# TRIWHEEL.net
KiCad netlist of a schematic drawn in EAGLE
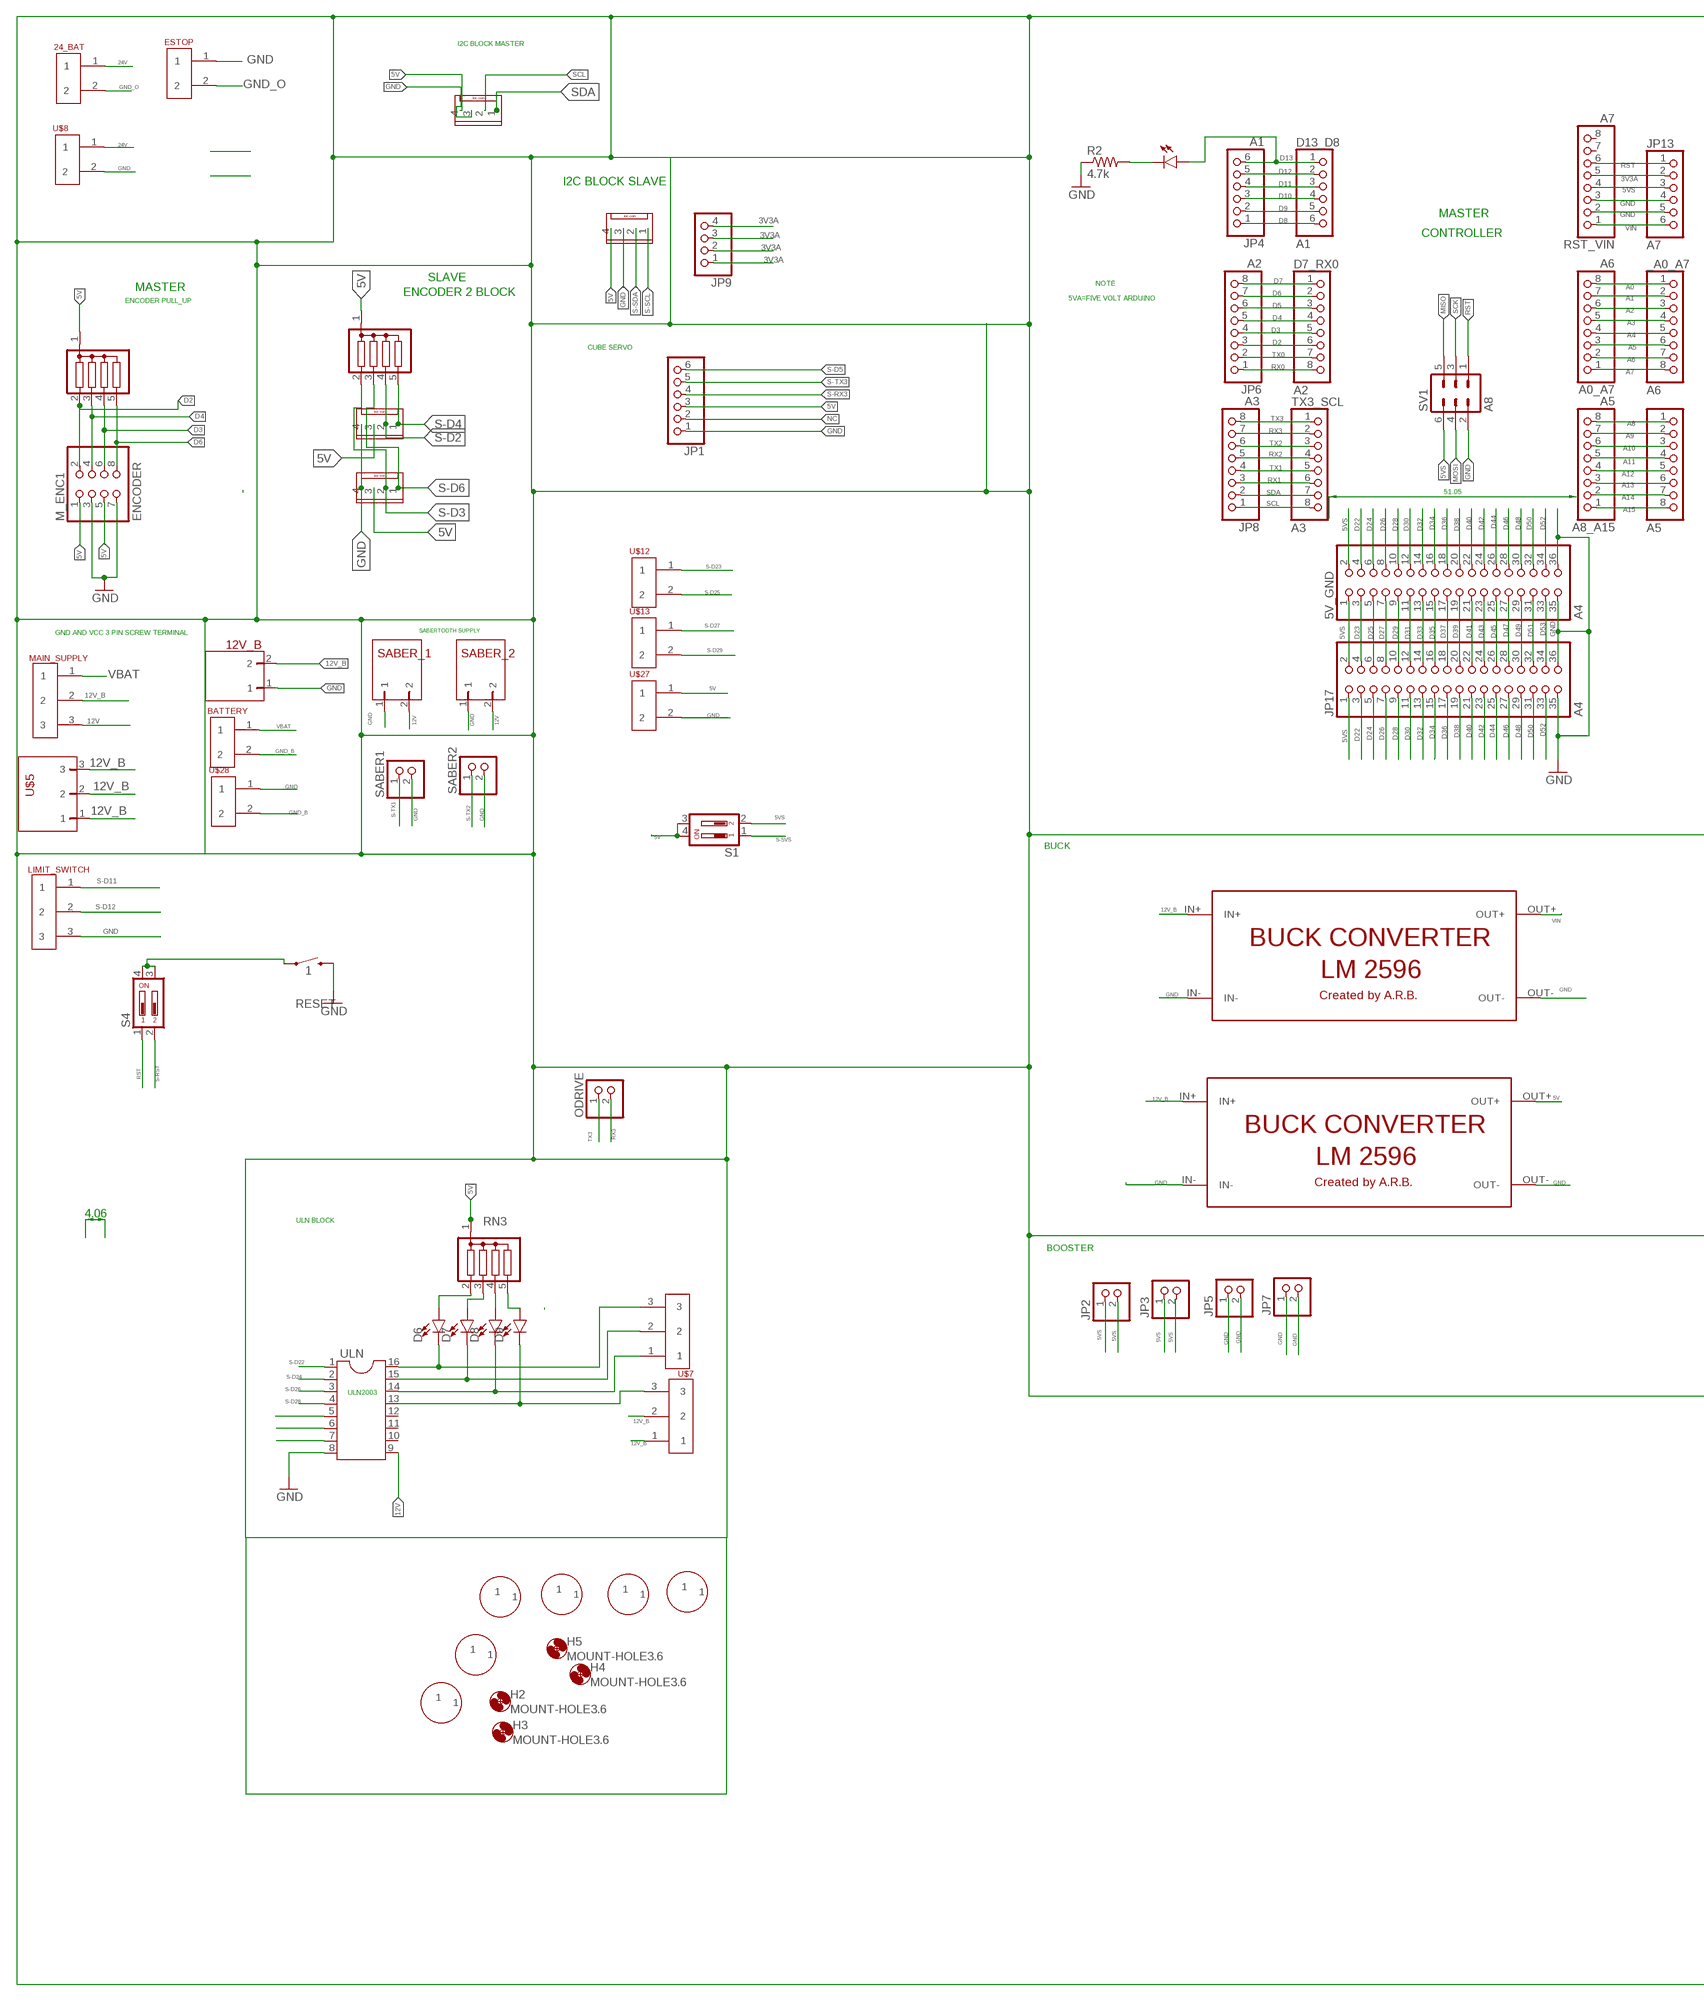
[diagram p0: schematic, sheet 1, part 1 of 2]
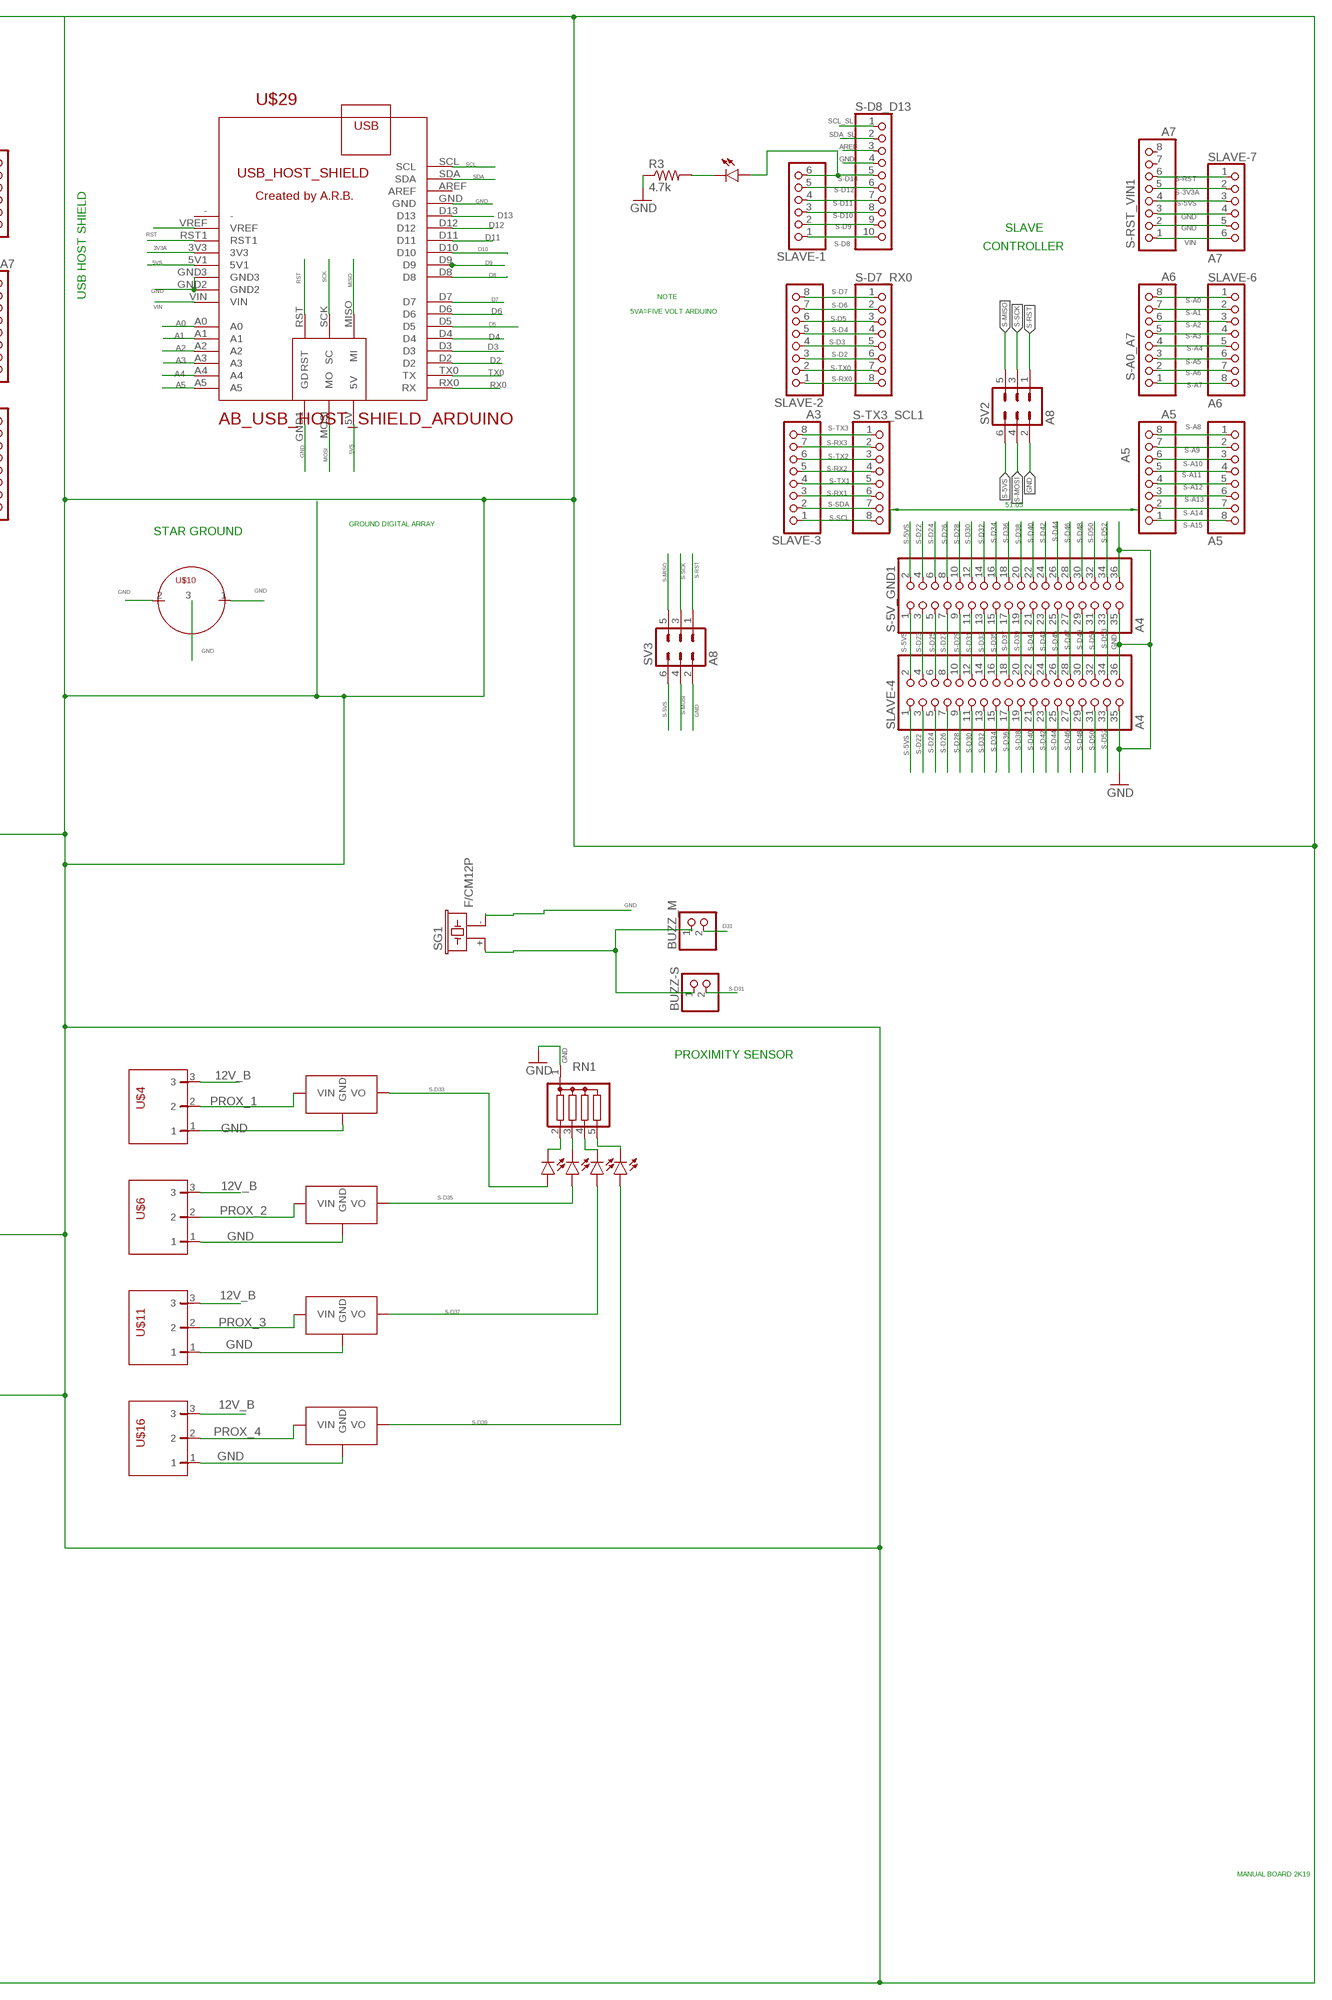
[diagram p1: schematic, sheet 1, part 2 of 2]

(export (version "E")
  (design (tool "Eeschema 10.0.6"))
  (components
    (comp (ref "5V_GND")
      (value "A4")
      (footprint "eagle-import:2X18")
      (libsource (lib "eagle-import") (part "PINHD-2X18"))
    )
    (comp (ref "12V_B")
      (value "AB_RIGHT_TER_BLK")
      (footprint "eagle-import:AB_RIGHT_TER_BLK")
      (libsource (lib "eagle-import") (part "AB_RIGHT_TER_BLK"))
    )
    (comp (ref "24_BAT")
      (value "AB_SCREW_TERMINAL_5MM_2PIN")
      (footprint "eagle-import:AB_SCREW_TERMINAL_5MM_2PIN")
      (libsource (lib "eagle-import") (part "AB_SCREW_TERMINAL_5MM_2PIN"))
    )
    (comp (ref "A0_A7")
      (value "A6")
      (footprint "eagle-import:1X08")
      (libsource (lib "eagle-import") (part "PINHD-1X8"))
    )
    (comp (ref "A5")
      (value "A5")
      (footprint "eagle-import:1X08")
      (libsource (lib "eagle-import") (part "PINHD-1X8"))
    )
    (comp (ref "A8_A15")
      (value "A5")
      (footprint "eagle-import:1X08")
      (libsource (lib "eagle-import") (part "PINHD-1X8"))
    )
    (comp (ref "BATTERY")
      (value "AB_SCREW_TERMINAL_5MM_2PIN")
      (footprint "eagle-import:AB_SCREW_TERMINAL_5MM_2PIN")
      (libsource (lib "eagle-import") (part "AB_SCREW_TERMINAL_5MM_2PIN"))
    )
    (comp (ref "BUZZ-S")
      (value "PINHD-1X2")
      (footprint "eagle-import:1X02")
      (libsource (lib "eagle-import") (part "PINHD-1X2"))
    )
    (comp (ref "BUZZ_M")
      (value "PINHD-1X2")
      (footprint "eagle-import:1X02")
      (libsource (lib "eagle-import") (part "PINHD-1X2"))
    )
    (comp (ref "D1")
      (value "LED-3MM-NO_SILK")
      (footprint "eagle-import:LED_3MM-NS")
      (libsource (lib "eagle-import") (part "LED-3MM-NO_SILK"))
    )
    (comp (ref "D2")
      (value "LED-3MM-NO_SILK")
      (footprint "eagle-import:LED_3MM-NS")
      (libsource (lib "eagle-import") (part "LED-3MM-NO_SILK"))
    )
    (comp (ref "D3")
      (value "LED-3MM-NO_SILK")
      (footprint "eagle-import:LED_3MM-NS")
      (libsource (lib "eagle-import") (part "LED-3MM-NO_SILK"))
    )
    (comp (ref "D4")
      (value "LED-3MM-NO_SILK")
      (footprint "eagle-import:LED_3MM-NS")
      (libsource (lib "eagle-import") (part "LED-3MM-NO_SILK"))
    )
    (comp (ref "D5")
      (value "LED-3MM-NO_SILK")
      (footprint "eagle-import:LED_3MM-NS")
      (libsource (lib "eagle-import") (part "LED-3MM-NO_SILK"))
    )
    (comp (ref "D6")
      (value "LED-3MM-NO_SILK")
      (footprint "eagle-import:LED_3MM-NS")
      (libsource (lib "eagle-import") (part "LED-3MM-NO_SILK"))
    )
    (comp (ref "D7")
      (value "LED-3MM-NO_SILK")
      (footprint "eagle-import:LED_3MM-NS")
      (libsource (lib "eagle-import") (part "LED-3MM-NO_SILK"))
    )
    (comp (ref "D7_RX0")
      (value "A2")
      (footprint "eagle-import:1X08")
      (libsource (lib "eagle-import") (part "PINHD-1X8"))
    )
    (comp (ref "D8")
      (value "LED-3MM-NO_SILK")
      (footprint "eagle-import:LED_3MM-NS")
      (libsource (lib "eagle-import") (part "LED-3MM-NO_SILK"))
    )
    (comp (ref "D9")
      (value "LED-3MM-NO_SILK")
      (footprint "eagle-import:LED_3MM-NS")
      (libsource (lib "eagle-import") (part "LED-3MM-NO_SILK"))
    )
    (comp (ref "D13")
      (value "LED-3MM-NO_SILK")
      (footprint "eagle-import:LED_3MM-NS")
      (libsource (lib "eagle-import") (part "LED-3MM-NO_SILK"))
    )
    (comp (ref "D13_D8")
      (value "A1")
      (footprint "eagle-import:1X06")
      (libsource (lib "eagle-import") (part "PINHD-1X6"))
    )
    (comp (ref "ESTOP")
      (value "AB_SCREW_TERMINAL_5MM_2PIN")
      (footprint "eagle-import:AB_SCREW_TERMINAL_5MM_2PIN")
      (libsource (lib "eagle-import") (part "AB_SCREW_TERMINAL_5MM_2PIN"))
    )
    (comp (ref "H2")
      (value "MOUNT-HOLE3.6")
      (footprint "eagle-import:3,6")
      (libsource (lib "eagle-import") (part "MOUNT-HOLE3.6"))
    )
    (comp (ref "H3")
      (value "MOUNT-HOLE3.6")
      (footprint "eagle-import:3,6")
      (libsource (lib "eagle-import") (part "MOUNT-HOLE3.6"))
    )
    (comp (ref "H4")
      (value "MOUNT-HOLE3.6")
      (footprint "eagle-import:3,6")
      (libsource (lib "eagle-import") (part "MOUNT-HOLE3.6"))
    )
    (comp (ref "H5")
      (value "MOUNT-HOLE3.6")
      (footprint "eagle-import:3,6")
      (libsource (lib "eagle-import") (part "MOUNT-HOLE3.6"))
    )
    (comp (ref "IMU_BLOCK")
      (value "AB_4PIN_LOC_CONNECTOR")
      (footprint "eagle-import:AB_4PIN_LOC_CONNECTOR")
      (libsource (lib "eagle-import") (part "AB_4PIN_LOC_CONNECTOR"))
    )
    (comp (ref "IMU_BLOCK-M")
      (value "AB_4PIN_LOC_CONNECTOR")
      (footprint "eagle-import:AB_4PIN_LOC_CONNECTOR")
      (libsource (lib "eagle-import") (part "AB_4PIN_LOC_CONNECTOR"))
    )
    (comp (ref "JP")
      (value "A5")
      (footprint "eagle-import:1X08")
      (libsource (lib "eagle-import") (part "PINHD-1X8"))
    )
    (comp (ref "JP1")
      (value "PINHD-1X6")
      (footprint "eagle-import:1X06")
      (libsource (lib "eagle-import") (part "PINHD-1X6"))
    )
    (comp (ref "JP2")
      (value "PINHD-1X2")
      (footprint "eagle-import:1X02")
      (libsource (lib "eagle-import") (part "PINHD-1X2"))
    )
    (comp (ref "JP3")
      (value "PINHD-1X2")
      (footprint "eagle-import:1X02")
      (libsource (lib "eagle-import") (part "PINHD-1X2"))
    )
    (comp (ref "JP4")
      (value "A1")
      (footprint "eagle-import:1X06")
      (libsource (lib "eagle-import") (part "PINHD-1X6"))
    )
    (comp (ref "JP5")
      (value "PINHD-1X2")
      (footprint "eagle-import:1X02")
      (libsource (lib "eagle-import") (part "PINHD-1X2"))
    )
    (comp (ref "JP6")
      (value "A2")
      (footprint "eagle-import:1X08")
      (libsource (lib "eagle-import") (part "PINHD-1X8"))
    )
    (comp (ref "JP7")
      (value "PINHD-1X2")
      (footprint "eagle-import:1X02")
      (libsource (lib "eagle-import") (part "PINHD-1X2"))
    )
    (comp (ref "JP8")
      (value "A3")
      (footprint "eagle-import:1X08")
      (libsource (lib "eagle-import") (part "PINHD-1X8"))
    )
    (comp (ref "JP9")
      (value "PINHD-1X4")
      (footprint "eagle-import:1X04")
      (libsource (lib "eagle-import") (part "PINHD-1X4"))
    )
    (comp (ref "JP13")
      (value "A7")
      (footprint "eagle-import:1X06")
      (libsource (lib "eagle-import") (part "PINHD-1X6"))
    )
    (comp (ref "JP17")
      (value "A4")
      (footprint "eagle-import:2X18")
      (libsource (lib "eagle-import") (part "PINHD-2X18"))
    )
    (comp (ref "LIMIT_SWITCH")
      (value "AB_SCREW_TER_5MM_3PIN")
      (footprint "eagle-import:AB_SCREW_TER_5MM_3PIN")
      (libsource (lib "eagle-import") (part "AB_SCREW_TER_5MM_3PIN"))
    )
    (comp (ref "MAIN_SUPPLY")
      (value "AB_SCREW_TER_5MM_3PIN")
      (footprint "eagle-import:AB_SCREW_TER_5MM_3PIN")
      (libsource (lib "eagle-import") (part "AB_SCREW_TER_5MM_3PIN"))
    )
    (comp (ref "MAIN_SUPPLY1")
      (value "AB_SCREW_TER_5MM_3PIN")
      (footprint "eagle-import:AB_SCREW_TER_5MM_3PIN")
      (libsource (lib "eagle-import") (part "AB_SCREW_TER_5MM_3PIN"))
    )
    (comp (ref "M_ENC1")
      (value "ENCODER")
      (footprint "eagle-import:2X04")
      (libsource (lib "eagle-import") (part "PINHD-2X4"))
    )
    (comp (ref "ODRIVE")
      (value "PINHD-1X2")
      (footprint "eagle-import:1X02")
      (libsource (lib "eagle-import") (part "PINHD-1X2"))
    )
    (comp (ref "PULL_RESISTOR-M")
      (value "G04R")
      (footprint "eagle-import:SIL5")
      (libsource (lib "eagle-import") (part "G04R"))
    )
    (comp (ref "R2")
      (value "4.7k")
      (footprint "eagle-import:0204_7")
      (libsource (lib "eagle-import") (part "R-US_0204/7"))
    )
    (comp (ref "R3")
      (value "4.7k")
      (footprint "eagle-import:0204_7")
      (libsource (lib "eagle-import") (part "R-US_0204/7"))
    )
    (comp (ref "RESET")
      (value "1")
      (footprint "eagle-import:TACTILE_SWITCH_PTH_6.0MM")
      (libsource (lib "eagle-import") (part "MOMENTARY-SWITCH-SPST-PTH-6.0MM"))
    )
    (comp (ref "RN1")
      (value "G04R")
      (footprint "eagle-import:SIL5")
      (libsource (lib "eagle-import") (part "G04R"))
    )
    (comp (ref "RN3")
      (value "G04R")
      (footprint "eagle-import:SIL5")
      (libsource (lib "eagle-import") (part "G04R"))
    )
    (comp (ref "RST_VIN")
      (value "A7")
      (footprint "eagle-import:1X08")
      (libsource (lib "eagle-import") (part "PINHD-1X8"))
    )
    (comp (ref "S-5V_GND1")
      (value "A4")
      (footprint "eagle-import:2X18")
      (libsource (lib "eagle-import") (part "PINHD-2X18"))
    )
    (comp (ref "S-A0_A7")
      (value "A6")
      (footprint "eagle-import:1X08")
      (libsource (lib "eagle-import") (part "PINHD-1X8"))
    )
    (comp (ref "S-D7_RX0")
      (value "A2")
      (footprint "eagle-import:1X08")
      (libsource (lib "eagle-import") (part "PINHD-1X8"))
    )
    (comp (ref "S-D8_D13")
      (value "PINHD-1X10")
      (footprint "eagle-import:1X10")
      (libsource (lib "eagle-import") (part "PINHD-1X10"))
    )
    (comp (ref "S-ENC")
      (value "G04R")
      (footprint "eagle-import:SIL5")
      (libsource (lib "eagle-import") (part "G04R"))
    )
    (comp (ref "S-RST_VIN1")
      (value "A7")
      (footprint "eagle-import:1X08")
      (libsource (lib "eagle-import") (part "PINHD-1X8"))
    )
    (comp (ref "S-TX3_SCL1")
      (value "A3")
      (footprint "eagle-import:1X08")
      (libsource (lib "eagle-import") (part "PINHD-1X8"))
    )
    (comp (ref "S1")
      (value "DIP02YL")
      (footprint "eagle-import:DIP02YL")
      (libsource (lib "eagle-import") (part "DIP02YL"))
    )
    (comp (ref "S4")
      (value "DIP02YL")
      (footprint "eagle-import:DIP02YL")
      (libsource (lib "eagle-import") (part "DIP02YL"))
    )
    (comp (ref "SABER1")
      (value "PINHD-1X2")
      (footprint "eagle-import:1X02")
      (libsource (lib "eagle-import") (part "PINHD-1X2"))
    )
    (comp (ref "SABER2")
      (value "PINHD-1X2")
      (footprint "eagle-import:1X02")
      (libsource (lib "eagle-import") (part "PINHD-1X2"))
    )
    (comp (ref "SABER_1")
      (value "AB_RIGHT_TER_BLK")
      (footprint "eagle-import:AB_RIGHT_TER_BLK")
      (libsource (lib "eagle-import") (part "AB_RIGHT_TER_BLK"))
    )
    (comp (ref "SABER_2")
      (value "AB_RIGHT_TER_BLK")
      (footprint "eagle-import:AB_RIGHT_TER_BLK")
      (libsource (lib "eagle-import") (part "AB_RIGHT_TER_BLK"))
    )
    (comp (ref "SG1")
      (value "F/CM12P")
      (footprint "eagle-import:F_CM12P")
      (libsource (lib "eagle-import") (part "F/CM12P"))
    )
    (comp (ref "SLAVE-1")
      (value "A1")
      (footprint "eagle-import:1X06")
      (libsource (lib "eagle-import") (part "PINHD-1X6"))
    )
    (comp (ref "SLAVE-2")
      (value "A2")
      (footprint "eagle-import:1X08")
      (libsource (lib "eagle-import") (part "PINHD-1X8"))
    )
    (comp (ref "SLAVE-3")
      (value "A3")
      (footprint "eagle-import:1X08")
      (libsource (lib "eagle-import") (part "PINHD-1X8"))
    )
    (comp (ref "SLAVE-4")
      (value "A4")
      (footprint "eagle-import:2X18")
      (libsource (lib "eagle-import") (part "PINHD-2X18"))
    )
    (comp (ref "SLAVE-6")
      (value "A6")
      (footprint "eagle-import:1X08")
      (libsource (lib "eagle-import") (part "PINHD-1X8"))
    )
    (comp (ref "SLAVE-7")
      (value "A7")
      (footprint "eagle-import:1X06")
      (libsource (lib "eagle-import") (part "PINHD-1X6"))
    )
    (comp (ref "SV1")
      (value "A8")
      (footprint "eagle-import:MA03-2")
      (libsource (lib "eagle-import") (part "MA03-2"))
    )
    (comp (ref "SV2")
      (value "A8")
      (footprint "eagle-import:MA03-2")
      (libsource (lib "eagle-import") (part "MA03-2"))
    )
    (comp (ref "SV3")
      (value "A8")
      (footprint "eagle-import:MA03-2")
      (libsource (lib "eagle-import") (part "MA03-2"))
    )
    (comp (ref "S_A8_A15")
      (value "A5")
      (footprint "eagle-import:1X08")
      (libsource (lib "eagle-import") (part "PINHD-1X8"))
    )
    (comp (ref "TX3_SCL")
      (value "A3")
      (footprint "eagle-import:1X08")
      (libsource (lib "eagle-import") (part "PINHD-1X8"))
    )
    (comp (ref "U$1")
      (value "AB_LM2596_BUCK_CONVERTER")
      (footprint "eagle-import:AB_LM2596_BUCK_CONVERTER")
      (libsource (lib "eagle-import") (part "AB_LM2596_BUCK_CONVERTER"))
    )
    (comp (ref "U$2")
      (value "AB_LM2596_BUCK_CONVERTER")
      (footprint "eagle-import:AB_LM2596_BUCK_CONVERTER")
      (libsource (lib "eagle-import") (part "AB_LM2596_BUCK_CONVERTER"))
    )
    (comp (ref "U$4")
      (value "AB_RIGHT_TER_BLK_3PIN")
      (footprint "eagle-import:AB_RIGHT_TER_BLK_3PIN")
      (libsource (lib "eagle-import") (part "AB_RIGHT_TER_BLK_3PIN"))
    )
    (comp (ref "U$5")
      (value "AB_RIGHT_TER_BLK_3PIN")
      (footprint "eagle-import:AB_RIGHT_TER_BLK_3PIN")
      (libsource (lib "eagle-import") (part "AB_RIGHT_TER_BLK_3PIN"))
    )
    (comp (ref "U$6")
      (value "AB_RIGHT_TER_BLK_3PIN")
      (footprint "eagle-import:AB_RIGHT_TER_BLK_3PIN")
      (libsource (lib "eagle-import") (part "AB_RIGHT_TER_BLK_3PIN"))
    )
    (comp (ref "U$7")
      (value "AB_SCREW_TER_5MM_3PIN")
      (footprint "eagle-import:AB_SCREW_TER_5MM_3PIN")
      (libsource (lib "eagle-import") (part "AB_SCREW_TER_5MM_3PIN"))
    )
    (comp (ref "U$8")
      (value "AB_SCREW_TERMINAL_5MM_2PIN")
      (footprint "eagle-import:AB_SCREW_TERMINAL_5MM_2PIN")
      (libsource (lib "eagle-import") (part "AB_SCREW_TERMINAL_5MM_2PIN"))
    )
    (comp (ref "U$9")
      (value "AB_PLATED_DRILL_160MIL")
      (footprint "eagle-import:AB_PLATED_DRILL_160MIL")
      (libsource (lib "eagle-import") (part "AB_PLATED_DRILL_160MIL"))
    )
    (comp (ref "U$10")
      (value "AB_JOINT_GND")
      (footprint "eagle-import:AB_JOINT_GND")
      (libsource (lib "eagle-import") (part "AB_JOINT_GND"))
    )
    (comp (ref "U$11")
      (value "AB_RIGHT_TER_BLK_3PIN")
      (footprint "eagle-import:AB_RIGHT_TER_BLK_3PIN")
      (libsource (lib "eagle-import") (part "AB_RIGHT_TER_BLK_3PIN"))
    )
    (comp (ref "U$12")
      (value "AB_SCREW_TERMINAL_5MM_2PIN")
      (footprint "eagle-import:AB_SCREW_TERMINAL_5MM_2PIN")
      (libsource (lib "eagle-import") (part "AB_SCREW_TERMINAL_5MM_2PIN"))
    )
    (comp (ref "U$13")
      (value "AB_SCREW_TERMINAL_5MM_2PIN")
      (footprint "eagle-import:AB_SCREW_TERMINAL_5MM_2PIN")
      (libsource (lib "eagle-import") (part "AB_SCREW_TERMINAL_5MM_2PIN"))
    )
    (comp (ref "U$15")
      (value "AB_PLATED_DRILL_160MIL")
      (footprint "eagle-import:AB_PLATED_DRILL_160MIL")
      (libsource (lib "eagle-import") (part "AB_PLATED_DRILL_160MIL"))
    )
    (comp (ref "U$16")
      (value "AB_RIGHT_TER_BLK_3PIN")
      (footprint "eagle-import:AB_RIGHT_TER_BLK_3PIN")
      (libsource (lib "eagle-import") (part "AB_RIGHT_TER_BLK_3PIN"))
    )
    (comp (ref "U$17")
      (value "AB_7805_FLAT")
      (footprint "eagle-import:AB_7805_FLAT")
      (libsource (lib "eagle-import") (part "AB_7805_FLAT"))
    )
    (comp (ref "U$18")
      (value "AB_7805_FLAT")
      (footprint "eagle-import:AB_7805_FLAT")
      (libsource (lib "eagle-import") (part "AB_7805_FLAT"))
    )
    (comp (ref "U$19")
      (value "AB_7805_FLAT")
      (footprint "eagle-import:AB_7805_FLAT")
      (libsource (lib "eagle-import") (part "AB_7805_FLAT"))
    )
    (comp (ref "U$20")
      (value "AB_7805_FLAT")
      (footprint "eagle-import:AB_7805_FLAT")
      (libsource (lib "eagle-import") (part "AB_7805_FLAT"))
    )
    (comp (ref "U$21")
      (value "en1")
      (footprint "eagle-import:AB_4PIN_LOC_CONNECTOR")
      (libsource (lib "eagle-import") (part "AB_4PIN_LOC_CONNECTOR"))
    )
    (comp (ref "U$22")
      (value "en2")
      (footprint "eagle-import:AB_4PIN_LOC_CONNECTOR")
      (libsource (lib "eagle-import") (part "AB_4PIN_LOC_CONNECTOR"))
    )
    (comp (ref "U$23")
      (value "AB_PLATED_DRILL_160MIL")
      (footprint "eagle-import:AB_PLATED_DRILL_160MIL")
      (libsource (lib "eagle-import") (part "AB_PLATED_DRILL_160MIL"))
    )
    (comp (ref "U$24")
      (value "AB_PLATED_DRILL_160MIL")
      (footprint "eagle-import:AB_PLATED_DRILL_160MIL")
      (libsource (lib "eagle-import") (part "AB_PLATED_DRILL_160MIL"))
    )
    (comp (ref "U$25")
      (value "AB_PLATED_DRILL_160MIL")
      (footprint "eagle-import:AB_PLATED_DRILL_160MIL")
      (libsource (lib "eagle-import") (part "AB_PLATED_DRILL_160MIL"))
    )
    (comp (ref "U$26")
      (value "AB_PLATED_DRILL_160MIL")
      (footprint "eagle-import:AB_PLATED_DRILL_160MIL")
      (libsource (lib "eagle-import") (part "AB_PLATED_DRILL_160MIL"))
    )
    (comp (ref "U$27")
      (value "AB_SCREW_TERMINAL_5MM_2PIN")
      (footprint "eagle-import:AB_SCREW_TERMINAL_5MM_2PIN")
      (libsource (lib "eagle-import") (part "AB_SCREW_TERMINAL_5MM_2PIN"))
    )
    (comp (ref "U$28")
      (value "AB_SCREW_TERMINAL_5MM_2PIN")
      (footprint "eagle-import:AB_SCREW_TERMINAL_5MM_2PIN")
      (libsource (lib "eagle-import") (part "AB_SCREW_TERMINAL_5MM_2PIN"))
    )
    (comp (ref "U$29")
      (value "AB_USB_HOST_SHIELD_ARDUINO")
      (footprint "eagle-import:AB_USB_HOST_SHIELD_ARDUINO")
      (libsource (lib "eagle-import") (part "AB_USB_HOST_SHIELD_ARDUINO"))
    )
    (comp (ref "ULN")
      (value "DIL16")
      (footprint "eagle-import:DIL16")
      (libsource (lib "eagle-import") (part "DIL16"))
    )
    (comp (ref "_A0_A7")
      (value "A6")
      (footprint "eagle-import:1X08")
      (libsource (lib "eagle-import") (part "PINHD-1X8"))
    )
  )
  (nets
    (net (code "1") (name "/3V3A") (class "Default")
      (node (ref "JP13") (pin "2") (pinfunction "2_2") (pintype "passive"))
      (node (ref "JP9") (pin "1") (pinfunction "1_1") (pintype "passive"))
      (node (ref "JP9") (pin "2") (pinfunction "2_2") (pintype "passive"))
      (node (ref "JP9") (pin "3") (pinfunction "3_3") (pintype "passive"))
      (node (ref "JP9") (pin "4") (pinfunction "4_4") (pintype "passive"))
      (node (ref "RST_VIN") (pin "5") (pinfunction "5_5") (pintype "passive"))
      (node (ref "U$29") (pin "3V3") (pinfunction "3V3_3V3") (pintype "bidirectional"))
    )
    (net (code "2") (name "/24V") (class "Default")
      (node (ref "24_BAT") (pin "1") (pinfunction "1_1") (pintype "bidirectional"))
      (node (ref "U$8") (pin "1") (pinfunction "1_1") (pintype "bidirectional"))
    )
    (net (code "3") (name "/A0") (class "Default")
      (node (ref "A0_A7") (pin "8") (pinfunction "8_8") (pintype "passive"))
      (node (ref "U$29") (pin "A0") (pinfunction "A0_A0") (pintype "bidirectional"))
      (node (ref "_A0_A7") (pin "1") (pinfunction "1_1") (pintype "passive"))
    )
    (net (code "4") (name "/A1") (class "Default")
      (node (ref "A0_A7") (pin "7") (pinfunction "7_7") (pintype "passive"))
      (node (ref "U$29") (pin "A1") (pinfunction "A1_A1") (pintype "bidirectional"))
      (node (ref "_A0_A7") (pin "2") (pinfunction "2_2") (pintype "passive"))
    )
    (net (code "5") (name "/A2") (class "Default")
      (node (ref "A0_A7") (pin "6") (pinfunction "6_6") (pintype "passive"))
      (node (ref "U$29") (pin "A2") (pinfunction "A2_A2") (pintype "bidirectional"))
      (node (ref "_A0_A7") (pin "3") (pinfunction "3_3") (pintype "passive"))
    )
    (net (code "6") (name "/A3") (class "Default")
      (node (ref "A0_A7") (pin "5") (pinfunction "5_5") (pintype "passive"))
      (node (ref "U$29") (pin "A3") (pinfunction "A3_A3") (pintype "bidirectional"))
      (node (ref "_A0_A7") (pin "4") (pinfunction "4_4") (pintype "passive"))
    )
    (net (code "7") (name "/A4") (class "Default")
      (node (ref "A0_A7") (pin "4") (pinfunction "4_4") (pintype "passive"))
      (node (ref "U$29") (pin "A4") (pinfunction "A4_A4") (pintype "bidirectional"))
      (node (ref "_A0_A7") (pin "5") (pinfunction "5_5") (pintype "passive"))
    )
    (net (code "8") (name "/A5") (class "Default")
      (node (ref "A0_A7") (pin "3") (pinfunction "3_3") (pintype "passive"))
      (node (ref "U$29") (pin "A5") (pinfunction "A5_A5") (pintype "bidirectional"))
      (node (ref "_A0_A7") (pin "6") (pinfunction "6_6") (pintype "passive"))
    )
    (net (code "9") (name "/A6") (class "Default")
      (node (ref "A0_A7") (pin "2") (pinfunction "2_2") (pintype "passive"))
      (node (ref "_A0_A7") (pin "7") (pinfunction "7_7") (pintype "passive"))
    )
    (net (code "10") (name "/A7") (class "Default")
      (node (ref "A0_A7") (pin "1") (pinfunction "1_1") (pintype "passive"))
      (node (ref "_A0_A7") (pin "8") (pinfunction "8_8") (pintype "passive"))
    )
    (net (code "11") (name "/A8") (class "Default")
      (node (ref "A8_A15") (pin "8") (pinfunction "8_8") (pintype "passive"))
      (node (ref "JP") (pin "1") (pinfunction "1_1") (pintype "passive"))
    )
    (net (code "12") (name "/A9") (class "Default")
      (node (ref "A8_A15") (pin "7") (pinfunction "7_7") (pintype "passive"))
      (node (ref "JP") (pin "2") (pinfunction "2_2") (pintype "passive"))
    )
    (net (code "13") (name "/A10") (class "Default")
      (node (ref "A8_A15") (pin "6") (pinfunction "6_6") (pintype "passive"))
      (node (ref "JP") (pin "3") (pinfunction "3_3") (pintype "passive"))
    )
    (net (code "14") (name "/A11") (class "Default")
      (node (ref "A8_A15") (pin "5") (pinfunction "5_5") (pintype "passive"))
      (node (ref "JP") (pin "4") (pinfunction "4_4") (pintype "passive"))
    )
    (net (code "15") (name "/A12") (class "Default")
      (node (ref "A8_A15") (pin "4") (pinfunction "4_4") (pintype "passive"))
      (node (ref "JP") (pin "5") (pinfunction "5_5") (pintype "passive"))
    )
    (net (code "16") (name "/A13") (class "Default")
      (node (ref "A8_A15") (pin "3") (pinfunction "3_3") (pintype "passive"))
      (node (ref "JP") (pin "6") (pinfunction "6_6") (pintype "passive"))
    )
    (net (code "17") (name "/A14") (class "Default")
      (node (ref "A8_A15") (pin "2") (pinfunction "2_2") (pintype "passive"))
      (node (ref "JP") (pin "7") (pinfunction "7_7") (pintype "passive"))
    )
    (net (code "18") (name "/A15") (class "Default")
      (node (ref "A8_A15") (pin "1") (pinfunction "1_1") (pintype "passive"))
      (node (ref "JP") (pin "8") (pinfunction "8_8") (pintype "passive"))
    )
    (net (code "19") (name "/AREF") (class "Default")
      (node (ref "S-D8_D13") (pin "3") (pinfunction "3_3") (pintype "passive"))
    )
    (net (code "20") (name "/D5") (class "Default")
      (node (ref "D7_RX0") (pin "3") (pinfunction "3_3") (pintype "passive"))
      (node (ref "JP6") (pin "6") (pinfunction "6_6") (pintype "passive"))
      (node (ref "U$29") (pin "D5") (pinfunction "D5_D5") (pintype "bidirectional"))
    )
    (net (code "21") (name "/D7") (class "Default")
      (node (ref "D7_RX0") (pin "1") (pinfunction "1_1") (pintype "passive"))
      (node (ref "JP6") (pin "8") (pinfunction "8_8") (pintype "passive"))
      (node (ref "U$29") (pin "D7") (pinfunction "D7_D7") (pintype "bidirectional"))
    )
    (net (code "22") (name "/D8") (class "Default")
      (node (ref "D13_D8") (pin "6") (pinfunction "6_6") (pintype "passive"))
      (node (ref "JP4") (pin "1") (pinfunction "1_1") (pintype "passive"))
      (node (ref "U$29") (pin "D8") (pinfunction "D8_D8") (pintype "bidirectional"))
    )
    (net (code "23") (name "/D9") (class "Default")
      (node (ref "D13_D8") (pin "5") (pinfunction "5_5") (pintype "passive"))
      (node (ref "JP4") (pin "2") (pinfunction "2_2") (pintype "passive"))
      (node (ref "U$29") (pin "D9") (pinfunction "D9_D9") (pintype "bidirectional"))
    )
    (net (code "24") (name "/D10") (class "Default")
      (node (ref "D13_D8") (pin "4") (pinfunction "4_4") (pintype "passive"))
      (node (ref "JP4") (pin "3") (pinfunction "3_3") (pintype "passive"))
      (node (ref "U$29") (pin "D10") (pinfunction "D10_D10") (pintype "bidirectional"))
    )
    (net (code "25") (name "/D11") (class "Default")
      (node (ref "D13_D8") (pin "3") (pinfunction "3_3") (pintype "passive"))
      (node (ref "JP4") (pin "4") (pinfunction "4_4") (pintype "passive"))
      (node (ref "U$29") (pin "D11") (pinfunction "D11_D11") (pintype "bidirectional"))
    )
    (net (code "26") (name "/D12") (class "Default")
      (node (ref "D13_D8") (pin "2") (pinfunction "2_2") (pintype "passive"))
      (node (ref "JP4") (pin "5") (pinfunction "5_5") (pintype "passive"))
      (node (ref "U$29") (pin "D12") (pinfunction "D12_D12") (pintype "bidirectional"))
    )
    (net (code "27") (name "/D13") (class "Default")
      (node (ref "D13") (pin "A") (pinfunction "A_A") (pintype "passive"))
      (node (ref "D13_D8") (pin "1") (pinfunction "1_1") (pintype "passive"))
      (node (ref "JP4") (pin "6") (pinfunction "6_6") (pintype "passive"))
      (node (ref "U$29") (pin "D13") (pinfunction "D13_D13") (pintype "bidirectional"))
    )
    (net (code "28") (name "/D22") (class "Default")
      (node (ref "5V_GND") (pin "4") (pinfunction "4_4") (pintype "passive"))
      (node (ref "JP17") (pin "3") (pinfunction "3_3") (pintype "passive"))
    )
    (net (code "29") (name "/D23") (class "Default")
      (node (ref "5V_GND") (pin "3") (pinfunction "3_3") (pintype "passive"))
      (node (ref "JP17") (pin "4") (pinfunction "4_4") (pintype "passive"))
    )
    (net (code "30") (name "/D24") (class "Default")
      (node (ref "5V_GND") (pin "6") (pinfunction "6_6") (pintype "passive"))
      (node (ref "JP17") (pin "5") (pinfunction "5_5") (pintype "passive"))
    )
    (net (code "31") (name "/D25") (class "Default")
      (node (ref "5V_GND") (pin "5") (pinfunction "5_5") (pintype "passive"))
      (node (ref "JP17") (pin "6") (pinfunction "6_6") (pintype "passive"))
    )
    (net (code "32") (name "/D26") (class "Default")
      (node (ref "5V_GND") (pin "8") (pinfunction "8_8") (pintype "passive"))
      (node (ref "JP17") (pin "7") (pinfunction "7_7") (pintype "passive"))
    )
    (net (code "33") (name "/D27") (class "Default")
      (node (ref "5V_GND") (pin "7") (pinfunction "7_7") (pintype "passive"))
      (node (ref "JP17") (pin "8") (pinfunction "8_8") (pintype "passive"))
    )
    (net (code "34") (name "/D28") (class "Default")
      (node (ref "5V_GND") (pin "10") (pinfunction "10_10") (pintype "passive"))
      (node (ref "JP17") (pin "9") (pinfunction "9_9") (pintype "passive"))
    )
    (net (code "35") (name "/D29") (class "Default")
      (node (ref "5V_GND") (pin "9") (pinfunction "9_9") (pintype "passive"))
      (node (ref "JP17") (pin "10") (pinfunction "10_10") (pintype "passive"))
    )
    (net (code "36") (name "/D30") (class "Default")
      (node (ref "5V_GND") (pin "12") (pinfunction "12_12") (pintype "passive"))
      (node (ref "JP17") (pin "11") (pinfunction "11_11") (pintype "passive"))
    )
    (net (code "37") (name "/D31") (class "Default")
      (node (ref "5V_GND") (pin "11") (pinfunction "11_11") (pintype "passive"))
      (node (ref "BUZZ_M") (pin "2") (pinfunction "2_2") (pintype "passive"))
      (node (ref "JP17") (pin "12") (pinfunction "12_12") (pintype "passive"))
    )
    (net (code "38") (name "/D32") (class "Default")
      (node (ref "5V_GND") (pin "14") (pinfunction "14_14") (pintype "passive"))
      (node (ref "JP17") (pin "13") (pinfunction "13_13") (pintype "passive"))
    )
    (net (code "39") (name "/D33") (class "Default")
      (node (ref "5V_GND") (pin "13") (pinfunction "13_13") (pintype "passive"))
      (node (ref "JP17") (pin "14") (pinfunction "14_14") (pintype "passive"))
    )
    (net (code "40") (name "/D34") (class "Default")
      (node (ref "5V_GND") (pin "16") (pinfunction "16_16") (pintype "passive"))
      (node (ref "JP17") (pin "15") (pinfunction "15_15") (pintype "passive"))
    )
    (net (code "41") (name "/D35") (class "Default")
      (node (ref "5V_GND") (pin "15") (pinfunction "15_15") (pintype "passive"))
      (node (ref "JP17") (pin "16") (pinfunction "16_16") (pintype "passive"))
    )
    (net (code "42") (name "/D36") (class "Default")
      (node (ref "5V_GND") (pin "18") (pinfunction "18_18") (pintype "passive"))
      (node (ref "JP17") (pin "17") (pinfunction "17_17") (pintype "passive"))
    )
    (net (code "43") (name "/D37") (class "Default")
      (node (ref "5V_GND") (pin "17") (pinfunction "17_17") (pintype "passive"))
      (node (ref "JP17") (pin "18") (pinfunction "18_18") (pintype "passive"))
    )
    (net (code "44") (name "/D38") (class "Default")
      (node (ref "5V_GND") (pin "20") (pinfunction "20_20") (pintype "passive"))
      (node (ref "JP17") (pin "19") (pinfunction "19_19") (pintype "passive"))
    )
    (net (code "45") (name "/D39") (class "Default")
      (node (ref "5V_GND") (pin "19") (pinfunction "19_19") (pintype "passive"))
      (node (ref "JP17") (pin "20") (pinfunction "20_20") (pintype "passive"))
    )
    (net (code "46") (name "/D40") (class "Default")
      (node (ref "5V_GND") (pin "22") (pinfunction "22_22") (pintype "passive"))
      (node (ref "JP17") (pin "21") (pinfunction "21_21") (pintype "passive"))
    )
    (net (code "47") (name "/D41") (class "Default")
      (node (ref "5V_GND") (pin "21") (pinfunction "21_21") (pintype "passive"))
      (node (ref "JP17") (pin "22") (pinfunction "22_22") (pintype "passive"))
    )
    (net (code "48") (name "/D42") (class "Default")
      (node (ref "5V_GND") (pin "24") (pinfunction "24_24") (pintype "passive"))
      (node (ref "JP17") (pin "23") (pinfunction "23_23") (pintype "passive"))
    )
    (net (code "49") (name "/D43") (class "Default")
      (node (ref "5V_GND") (pin "23") (pinfunction "23_23") (pintype "passive"))
      (node (ref "JP17") (pin "24") (pinfunction "24_24") (pintype "passive"))
    )
    (net (code "50") (name "/D44") (class "Default")
      (node (ref "5V_GND") (pin "26") (pinfunction "26_26") (pintype "passive"))
      (node (ref "JP17") (pin "25") (pinfunction "25_25") (pintype "passive"))
    )
    (net (code "51") (name "/D45") (class "Default")
      (node (ref "5V_GND") (pin "25") (pinfunction "25_25") (pintype "passive"))
      (node (ref "JP17") (pin "26") (pinfunction "26_26") (pintype "passive"))
    )
    (net (code "52") (name "/D46") (class "Default")
      (node (ref "5V_GND") (pin "28") (pinfunction "28_28") (pintype "passive"))
      (node (ref "JP17") (pin "27") (pinfunction "27_27") (pintype "passive"))
    )
    (net (code "53") (name "/D47") (class "Default")
      (node (ref "5V_GND") (pin "27") (pinfunction "27_27") (pintype "passive"))
      (node (ref "JP17") (pin "28") (pinfunction "28_28") (pintype "passive"))
    )
    (net (code "54") (name "/D48") (class "Default")
      (node (ref "5V_GND") (pin "30") (pinfunction "30_30") (pintype "passive"))
      (node (ref "JP17") (pin "29") (pinfunction "29_29") (pintype "passive"))
    )
    (net (code "55") (name "/D49") (class "Default")
      (node (ref "5V_GND") (pin "29") (pinfunction "29_29") (pintype "passive"))
      (node (ref "JP17") (pin "30") (pinfunction "30_30") (pintype "passive"))
    )
    (net (code "56") (name "/D50") (class "Default")
      (node (ref "5V_GND") (pin "32") (pinfunction "32_32") (pintype "passive"))
      (node (ref "JP17") (pin "31") (pinfunction "31_31") (pintype "passive"))
    )
    (net (code "57") (name "/D51") (class "Default")
      (node (ref "5V_GND") (pin "31") (pinfunction "31_31") (pintype "passive"))
      (node (ref "JP17") (pin "32") (pinfunction "32_32") (pintype "passive"))
    )
    (net (code "58") (name "/D52") (class "Default")
      (node (ref "5V_GND") (pin "34") (pinfunction "34_34") (pintype "passive"))
      (node (ref "JP17") (pin "33") (pinfunction "33_33") (pintype "passive"))
    )
    (net (code "59") (name "/D53") (class "Default")
      (node (ref "5V_GND") (pin "33") (pinfunction "33_33") (pintype "passive"))
      (node (ref "JP17") (pin "34") (pinfunction "34_34") (pintype "passive"))
    )
    (net (code "60") (name "/GND_B") (class "Default")
      (node (ref "BATTERY") (pin "2") (pinfunction "2_2") (pintype "bidirectional"))
      (node (ref "U$28") (pin "2") (pinfunction "2_2") (pintype "bidirectional"))
    )
    (net (code "61") (name "/GND_O") (class "Default")
      (node (ref "24_BAT") (pin "2") (pinfunction "2_2") (pintype "bidirectional"))
      (node (ref "ESTOP") (pin "2") (pinfunction "2_2") (pintype "bidirectional"))
    )
    (net (code "62") (name "/PROX_1") (class "Default")
      (node (ref "U$17") (pin "1") (pinfunction "VIN_1") (pintype "bidirectional"))
      (node (ref "U$4") (pin "2") (pinfunction "2_2") (pintype "bidirectional"))
    )
    (net (code "63") (name "/PROX_2") (class "Default")
      (node (ref "U$18") (pin "1") (pinfunction "VIN_1") (pintype "bidirectional"))
      (node (ref "U$6") (pin "2") (pinfunction "2_2") (pintype "bidirectional"))
    )
    (net (code "64") (name "/PROX_3") (class "Default")
      (node (ref "U$11") (pin "2") (pinfunction "2_2") (pintype "bidirectional"))
      (node (ref "U$19") (pin "1") (pinfunction "VIN_1") (pintype "bidirectional"))
    )
    (net (code "65") (name "/PROX_4") (class "Default")
      (node (ref "U$16") (pin "2") (pinfunction "2_2") (pintype "bidirectional"))
      (node (ref "U$20") (pin "1") (pinfunction "VIN_1") (pintype "bidirectional"))
    )
    (net (code "66") (name "/RX0") (class "Default")
      (node (ref "D7_RX0") (pin "8") (pinfunction "8_8") (pintype "passive"))
      (node (ref "JP6") (pin "1") (pinfunction "1_1") (pintype "passive"))
      (node (ref "U$29") (pin "RX0") (pinfunction "RX_RX0") (pintype "bidirectional"))
    )
    (net (code "67") (name "/RX1") (class "Default")
      (node (ref "JP8") (pin "3") (pinfunction "3_3") (pintype "passive"))
      (node (ref "TX3_SCL") (pin "6") (pinfunction "6_6") (pintype "passive"))
    )
    (net (code "68") (name "/RX2") (class "Default")
      (node (ref "JP8") (pin "5") (pinfunction "5_5") (pintype "passive"))
      (node (ref "TX3_SCL") (pin "4") (pinfunction "4_4") (pintype "passive"))
    )
    (net (code "69") (name "/RX3") (class "Default")
      (node (ref "JP8") (pin "7") (pinfunction "7_7") (pintype "passive"))
      (node (ref "ODRIVE") (pin "2") (pinfunction "2_2") (pintype "passive"))
      (node (ref "TX3_SCL") (pin "2") (pinfunction "2_2") (pintype "passive"))
    )
    (net (code "70") (name "/S-3V3A") (class "Default")
      (node (ref "S-RST_VIN1") (pin "5") (pinfunction "5_5") (pintype "passive"))
      (node (ref "SLAVE-7") (pin "2") (pinfunction "2_2") (pintype "passive"))
    )
    (net (code "71") (name "/S-A0") (class "Default")
      (node (ref "S-A0_A7") (pin "8") (pinfunction "8_8") (pintype "passive"))
      (node (ref "SLAVE-6") (pin "1") (pinfunction "1_1") (pintype "passive"))
    )
    (net (code "72") (name "/S-A1") (class "Default")
      (node (ref "S-A0_A7") (pin "7") (pinfunction "7_7") (pintype "passive"))
      (node (ref "SLAVE-6") (pin "2") (pinfunction "2_2") (pintype "passive"))
    )
    (net (code "73") (name "/S-A2") (class "Default")
      (node (ref "S-A0_A7") (pin "6") (pinfunction "6_6") (pintype "passive"))
      (node (ref "SLAVE-6") (pin "3") (pinfunction "3_3") (pintype "passive"))
    )
    (net (code "74") (name "/S-A3") (class "Default")
      (node (ref "S-A0_A7") (pin "5") (pinfunction "5_5") (pintype "passive"))
      (node (ref "SLAVE-6") (pin "4") (pinfunction "4_4") (pintype "passive"))
    )
    (net (code "75") (name "/S-A4") (class "Default")
      (node (ref "S-A0_A7") (pin "4") (pinfunction "4_4") (pintype "passive"))
      (node (ref "SLAVE-6") (pin "5") (pinfunction "5_5") (pintype "passive"))
    )
    (net (code "76") (name "/S-A5") (class "Default")
      (node (ref "S-A0_A7") (pin "3") (pinfunction "3_3") (pintype "passive"))
      (node (ref "SLAVE-6") (pin "6") (pinfunction "6_6") (pintype "passive"))
    )
    (net (code "77") (name "/S-A6") (class "Default")
      (node (ref "S-A0_A7") (pin "2") (pinfunction "2_2") (pintype "passive"))
      (node (ref "SLAVE-6") (pin "7") (pinfunction "7_7") (pintype "passive"))
    )
    (net (code "78") (name "/S-A7") (class "Default")
      (node (ref "S-A0_A7") (pin "1") (pinfunction "1_1") (pintype "passive"))
      (node (ref "SLAVE-6") (pin "8") (pinfunction "8_8") (pintype "passive"))
    )
    (net (code "79") (name "/S-A8") (class "Default")
      (node (ref "A5") (pin "8") (pinfunction "8_8") (pintype "passive"))
      (node (ref "S_A8_A15") (pin "1") (pinfunction "1_1") (pintype "passive"))
    )
    (net (code "80") (name "/S-A9") (class "Default")
      (node (ref "A5") (pin "7") (pinfunction "7_7") (pintype "passive"))
      (node (ref "S_A8_A15") (pin "2") (pinfunction "2_2") (pintype "passive"))
    )
    (net (code "81") (name "/S-A10") (class "Default")
      (node (ref "A5") (pin "6") (pinfunction "6_6") (pintype "passive"))
      (node (ref "S_A8_A15") (pin "3") (pinfunction "3_3") (pintype "passive"))
    )
    (net (code "82") (name "/S-A11") (class "Default")
      (node (ref "A5") (pin "5") (pinfunction "5_5") (pintype "passive"))
      (node (ref "S_A8_A15") (pin "4") (pinfunction "4_4") (pintype "passive"))
    )
    (net (code "83") (name "/S-A12") (class "Default")
      (node (ref "A5") (pin "4") (pinfunction "4_4") (pintype "passive"))
      (node (ref "S_A8_A15") (pin "5") (pinfunction "5_5") (pintype "passive"))
    )
    (net (code "84") (name "/S-A13") (class "Default")
      (node (ref "A5") (pin "3") (pinfunction "3_3") (pintype "passive"))
      (node (ref "S_A8_A15") (pin "6") (pinfunction "6_6") (pintype "passive"))
    )
    (net (code "85") (name "/S-A14") (class "Default")
      (node (ref "A5") (pin "2") (pinfunction "2_2") (pintype "passive"))
      (node (ref "S_A8_A15") (pin "7") (pinfunction "7_7") (pintype "passive"))
    )
    (net (code "86") (name "/S-A15") (class "Default")
      (node (ref "A5") (pin "1") (pinfunction "1_1") (pintype "passive"))
      (node (ref "S_A8_A15") (pin "8") (pinfunction "8_8") (pintype "passive"))
    )
    (net (code "87") (name "/S-D7") (class "Default")
      (node (ref "S-D7_RX0") (pin "1") (pinfunction "1_1") (pintype "passive"))
      (node (ref "SLAVE-2") (pin "8") (pinfunction "8_8") (pintype "passive"))
    )
    (net (code "88") (name "/S-D8") (class "Default")
      (node (ref "S-D8_D13") (pin "10") (pinfunction "10_10") (pintype "passive"))
      (node (ref "SLAVE-1") (pin "1") (pinfunction "1_1") (pintype "passive"))
    )
    (net (code "89") (name "/S-D9") (class "Default")
      (node (ref "S-D8_D13") (pin "9") (pinfunction "9_9") (pintype "passive"))
      (node (ref "SLAVE-1") (pin "2") (pinfunction "2_2") (pintype "passive"))
    )
    (net (code "90") (name "/S-D10") (class "Default")
      (node (ref "S-D8_D13") (pin "8") (pinfunction "8_8") (pintype "passive"))
      (node (ref "SLAVE-1") (pin "3") (pinfunction "3_3") (pintype "passive"))
    )
    (net (code "91") (name "/S-D11") (class "Default")
      (node (ref "LIMIT_SWITCH") (pin "1") (pinfunction "1_1") (pintype "bidirectional"))
      (node (ref "S-D8_D13") (pin "7") (pinfunction "7_7") (pintype "passive"))
      (node (ref "SLAVE-1") (pin "4") (pinfunction "4_4") (pintype "passive"))
    )
    (net (code "92") (name "/S-D12") (class "Default")
      (node (ref "LIMIT_SWITCH") (pin "2") (pinfunction "2_2") (pintype "bidirectional"))
      (node (ref "S-D8_D13") (pin "6") (pinfunction "6_6") (pintype "passive"))
      (node (ref "SLAVE-1") (pin "5") (pinfunction "5_5") (pintype "passive"))
    )
    (net (code "93") (name "/S-D13") (class "Default")
      (node (ref "D5") (pin "A") (pinfunction "A_A") (pintype "passive"))
      (node (ref "S-D8_D13") (pin "5") (pinfunction "5_5") (pintype "passive"))
      (node (ref "SLAVE-1") (pin "6") (pinfunction "6_6") (pintype "passive"))
    )
    (net (code "94") (name "/S-D22") (class "Default")
      (node (ref "S-5V_GND1") (pin "4") (pinfunction "4_4") (pintype "passive"))
      (node (ref "SLAVE-4") (pin "3") (pinfunction "3_3") (pintype "passive"))
      (node (ref "ULN") (pin "1") (pinfunction "1_1") (pintype "passive"))
    )
    (net (code "95") (name "/S-D23") (class "Default")
      (node (ref "S-5V_GND1") (pin "3") (pinfunction "3_3") (pintype "passive"))
      (node (ref "SLAVE-4") (pin "4") (pinfunction "4_4") (pintype "passive"))
      (node (ref "U$12") (pin "1") (pinfunction "1_1") (pintype "bidirectional"))
    )
    (net (code "96") (name "/S-D24") (class "Default")
      (node (ref "S-5V_GND1") (pin "6") (pinfunction "6_6") (pintype "passive"))
      (node (ref "SLAVE-4") (pin "5") (pinfunction "5_5") (pintype "passive"))
      (node (ref "ULN") (pin "2") (pinfunction "2_2") (pintype "passive"))
    )
    (net (code "97") (name "/S-D25") (class "Default")
      (node (ref "S-5V_GND1") (pin "5") (pinfunction "5_5") (pintype "passive"))
      (node (ref "SLAVE-4") (pin "6") (pinfunction "6_6") (pintype "passive"))
      (node (ref "U$12") (pin "2") (pinfunction "2_2") (pintype "bidirectional"))
    )
    (net (code "98") (name "/S-D26") (class "Default")
      (node (ref "S-5V_GND1") (pin "8") (pinfunction "8_8") (pintype "passive"))
      (node (ref "SLAVE-4") (pin "7") (pinfunction "7_7") (pintype "passive"))
      (node (ref "ULN") (pin "3") (pinfunction "3_3") (pintype "passive"))
    )
    (net (code "99") (name "/S-D27") (class "Default")
      (node (ref "S-5V_GND1") (pin "7") (pinfunction "7_7") (pintype "passive"))
      (node (ref "SLAVE-4") (pin "8") (pinfunction "8_8") (pintype "passive"))
      (node (ref "U$13") (pin "1") (pinfunction "1_1") (pintype "bidirectional"))
    )
    (net (code "100") (name "/S-D28") (class "Default")
      (node (ref "S-5V_GND1") (pin "10") (pinfunction "10_10") (pintype "passive"))
      (node (ref "SLAVE-4") (pin "9") (pinfunction "9_9") (pintype "passive"))
      (node (ref "ULN") (pin "4") (pinfunction "4_4") (pintype "passive"))
    )
    (net (code "101") (name "/S-D29") (class "Default")
      (node (ref "S-5V_GND1") (pin "9") (pinfunction "9_9") (pintype "passive"))
      (node (ref "SLAVE-4") (pin "10") (pinfunction "10_10") (pintype "passive"))
      (node (ref "U$13") (pin "2") (pinfunction "2_2") (pintype "bidirectional"))
    )
    (net (code "102") (name "/S-D30") (class "Default")
      (node (ref "S-5V_GND1") (pin "12") (pinfunction "12_12") (pintype "passive"))
      (node (ref "SLAVE-4") (pin "11") (pinfunction "11_11") (pintype "passive"))
    )
    (net (code "103") (name "/S-D31") (class "Default")
      (node (ref "BUZZ-S") (pin "2") (pinfunction "2_2") (pintype "passive"))
      (node (ref "S-5V_GND1") (pin "11") (pinfunction "11_11") (pintype "passive"))
      (node (ref "SLAVE-4") (pin "12") (pinfunction "12_12") (pintype "passive"))
    )
    (net (code "104") (name "/S-D32") (class "Default")
      (node (ref "S-5V_GND1") (pin "14") (pinfunction "14_14") (pintype "passive"))
      (node (ref "SLAVE-4") (pin "13") (pinfunction "13_13") (pintype "passive"))
    )
    (net (code "105") (name "/S-D33") (class "Default")
      (node (ref "D1") (pin "A") (pinfunction "A_A") (pintype "passive"))
      (node (ref "S-5V_GND1") (pin "13") (pinfunction "13_13") (pintype "passive"))
      (node (ref "SLAVE-4") (pin "14") (pinfunction "14_14") (pintype "passive"))
      (node (ref "U$17") (pin "3") (pinfunction "VO_3") (pintype "bidirectional"))
    )
    (net (code "106") (name "/S-D34") (class "Default")
      (node (ref "S-5V_GND1") (pin "16") (pinfunction "16_16") (pintype "passive"))
      (node (ref "SLAVE-4") (pin "15") (pinfunction "15_15") (pintype "passive"))
    )
    (net (code "107") (name "/S-D35") (class "Default")
      (node (ref "D2") (pin "A") (pinfunction "A_A") (pintype "passive"))
      (node (ref "S-5V_GND1") (pin "15") (pinfunction "15_15") (pintype "passive"))
      (node (ref "SLAVE-4") (pin "16") (pinfunction "16_16") (pintype "passive"))
      (node (ref "U$18") (pin "3") (pinfunction "VO_3") (pintype "bidirectional"))
    )
    (net (code "108") (name "/S-D36") (class "Default")
      (node (ref "S-5V_GND1") (pin "18") (pinfunction "18_18") (pintype "passive"))
      (node (ref "SLAVE-4") (pin "17") (pinfunction "17_17") (pintype "passive"))
    )
    (net (code "109") (name "/S-D37") (class "Default")
      (node (ref "D3") (pin "A") (pinfunction "A_A") (pintype "passive"))
      (node (ref "S-5V_GND1") (pin "17") (pinfunction "17_17") (pintype "passive"))
      (node (ref "SLAVE-4") (pin "18") (pinfunction "18_18") (pintype "passive"))
      (node (ref "U$19") (pin "3") (pinfunction "VO_3") (pintype "bidirectional"))
    )
    (net (code "110") (name "/S-D38") (class "Default")
      (node (ref "S-5V_GND1") (pin "20") (pinfunction "20_20") (pintype "passive"))
      (node (ref "SLAVE-4") (pin "19") (pinfunction "19_19") (pintype "passive"))
    )
    (net (code "111") (name "/S-D39") (class "Default")
      (node (ref "D4") (pin "A") (pinfunction "A_A") (pintype "passive"))
      (node (ref "S-5V_GND1") (pin "19") (pinfunction "19_19") (pintype "passive"))
      (node (ref "SLAVE-4") (pin "20") (pinfunction "20_20") (pintype "passive"))
      (node (ref "U$20") (pin "3") (pinfunction "VO_3") (pintype "bidirectional"))
    )
    (net (code "112") (name "/S-D40") (class "Default")
      (node (ref "S-5V_GND1") (pin "22") (pinfunction "22_22") (pintype "passive"))
      (node (ref "SLAVE-4") (pin "21") (pinfunction "21_21") (pintype "passive"))
    )
    (net (code "113") (name "/S-D41") (class "Default")
      (node (ref "S-5V_GND1") (pin "21") (pinfunction "21_21") (pintype "passive"))
      (node (ref "SLAVE-4") (pin "22") (pinfunction "22_22") (pintype "passive"))
    )
    (net (code "114") (name "/S-D42") (class "Default")
      (node (ref "S-5V_GND1") (pin "24") (pinfunction "24_24") (pintype "passive"))
      (node (ref "SLAVE-4") (pin "23") (pinfunction "23_23") (pintype "passive"))
    )
    (net (code "115") (name "/S-D43") (class "Default")
      (node (ref "S-5V_GND1") (pin "23") (pinfunction "23_23") (pintype "passive"))
      (node (ref "SLAVE-4") (pin "24") (pinfunction "24_24") (pintype "passive"))
    )
    (net (code "116") (name "/S-D44") (class "Default")
      (node (ref "S-5V_GND1") (pin "26") (pinfunction "26_26") (pintype "passive"))
      (node (ref "SLAVE-4") (pin "25") (pinfunction "25_25") (pintype "passive"))
    )
    (net (code "117") (name "/S-D45") (class "Default")
      (node (ref "S-5V_GND1") (pin "25") (pinfunction "25_25") (pintype "passive"))
      (node (ref "SLAVE-4") (pin "26") (pinfunction "26_26") (pintype "passive"))
    )
    (net (code "118") (name "/S-D46") (class "Default")
      (node (ref "S-5V_GND1") (pin "28") (pinfunction "28_28") (pintype "passive"))
      (node (ref "SLAVE-4") (pin "27") (pinfunction "27_27") (pintype "passive"))
    )
    (net (code "119") (name "/S-D47") (class "Default")
      (node (ref "S-5V_GND1") (pin "27") (pinfunction "27_27") (pintype "passive"))
      (node (ref "SLAVE-4") (pin "28") (pinfunction "28_28") (pintype "passive"))
    )
    (net (code "120") (name "/S-D48") (class "Default")
      (node (ref "S-5V_GND1") (pin "30") (pinfunction "30_30") (pintype "passive"))
      (node (ref "SLAVE-4") (pin "29") (pinfunction "29_29") (pintype "passive"))
    )
    (net (code "121") (name "/S-D49") (class "Default")
      (node (ref "S-5V_GND1") (pin "29") (pinfunction "29_29") (pintype "passive"))
      (node (ref "SLAVE-4") (pin "30") (pinfunction "30_30") (pintype "passive"))
    )
    (net (code "122") (name "/S-D50") (class "Default")
      (node (ref "S-5V_GND1") (pin "32") (pinfunction "32_32") (pintype "passive"))
      (node (ref "SLAVE-4") (pin "31") (pinfunction "31_31") (pintype "passive"))
    )
    (net (code "123") (name "/S-D51") (class "Default")
      (node (ref "S-5V_GND1") (pin "31") (pinfunction "31_31") (pintype "passive"))
      (node (ref "SLAVE-4") (pin "32") (pinfunction "32_32") (pintype "passive"))
    )
    (net (code "124") (name "/S-D52") (class "Default")
      (node (ref "S-5V_GND1") (pin "34") (pinfunction "34_34") (pintype "passive"))
      (node (ref "SLAVE-4") (pin "33") (pinfunction "33_33") (pintype "passive"))
    )
    (net (code "125") (name "/S-D53") (class "Default")
      (node (ref "S-5V_GND1") (pin "33") (pinfunction "33_33") (pintype "passive"))
      (node (ref "SLAVE-4") (pin "34") (pinfunction "34_34") (pintype "passive"))
    )
    (net (code "126") (name "/S-RX0") (class "Default")
      (node (ref "S-D7_RX0") (pin "8") (pinfunction "8_8") (pintype "passive"))
      (node (ref "SLAVE-2") (pin "1") (pinfunction "1_1") (pintype "passive"))
    )
    (net (code "127") (name "/S-RX1") (class "Default")
      (node (ref "S-TX3_SCL1") (pin "6") (pinfunction "6_6") (pintype "passive"))
      (node (ref "SLAVE-3") (pin "3") (pinfunction "3_3") (pintype "passive"))
    )
    (net (code "128") (name "/S-RX2") (class "Default")
      (node (ref "S-TX3_SCL1") (pin "4") (pinfunction "4_4") (pintype "passive"))
      (node (ref "SLAVE-3") (pin "5") (pinfunction "5_5") (pintype "passive"))
    )
    (net (code "129") (name "/S-TX0") (class "Default")
      (node (ref "S-D7_RX0") (pin "7") (pinfunction "7_7") (pintype "passive"))
      (node (ref "SLAVE-2") (pin "2") (pinfunction "2_2") (pintype "passive"))
    )
    (net (code "130") (name "/S-TX1") (class "Default")
      (node (ref "S-TX3_SCL1") (pin "5") (pinfunction "5_5") (pintype "passive"))
      (node (ref "SABER1") (pin "1") (pinfunction "1_1") (pintype "passive"))
      (node (ref "SLAVE-3") (pin "4") (pinfunction "4_4") (pintype "passive"))
    )
    (net (code "131") (name "/S-TX2") (class "Default")
      (node (ref "S-TX3_SCL1") (pin "3") (pinfunction "3_3") (pintype "passive"))
      (node (ref "SABER2") (pin "1") (pinfunction "1_1") (pintype "passive"))
      (node (ref "SLAVE-3") (pin "6") (pinfunction "6_6") (pintype "passive"))
    )
    (net (code "132") (name "/SCL_SL") (class "Default")
      (node (ref "S-D8_D13") (pin "1") (pinfunction "1_1") (pintype "passive"))
    )
    (net (code "133") (name "/SDA_SL") (class "Default")
      (node (ref "S-D8_D13") (pin "2") (pinfunction "2_2") (pintype "passive"))
    )
    (net (code "134") (name "/TX0") (class "Default")
      (node (ref "D7_RX0") (pin "7") (pinfunction "7_7") (pintype "passive"))
      (node (ref "JP6") (pin "2") (pinfunction "2_2") (pintype "passive"))
      (node (ref "U$29") (pin "TX0") (pinfunction "TX_TX0") (pintype "bidirectional"))
    )
    (net (code "135") (name "/TX1") (class "Default")
      (node (ref "JP8") (pin "4") (pinfunction "4_4") (pintype "passive"))
      (node (ref "TX3_SCL") (pin "5") (pinfunction "5_5") (pintype "passive"))
    )
    (net (code "136") (name "/TX2") (class "Default")
      (node (ref "JP8") (pin "6") (pinfunction "6_6") (pintype "passive"))
      (node (ref "TX3_SCL") (pin "3") (pinfunction "3_3") (pintype "passive"))
    )
    (net (code "137") (name "/TX3") (class "Default")
      (node (ref "JP8") (pin "8") (pinfunction "8_8") (pintype "passive"))
      (node (ref "ODRIVE") (pin "1") (pinfunction "1_1") (pintype "passive"))
      (node (ref "TX3_SCL") (pin "1") (pinfunction "1_1") (pintype "passive"))
    )
    (net (code "138") (name "/VBAT") (class "Default")
      (node (ref "BATTERY") (pin "1") (pinfunction "1_1") (pintype "bidirectional"))
      (node (ref "MAIN_SUPPLY") (pin "1") (pinfunction "1_1") (pintype "bidirectional"))
    )
    (net (code "139") (name "/VIN") (class "Default")
      (node (ref "JP13") (pin "6") (pinfunction "6_6") (pintype "passive"))
      (node (ref "RST_VIN") (pin "1") (pinfunction "1_1") (pintype "passive"))
      (node (ref "S-RST_VIN1") (pin "1") (pinfunction "1_1") (pintype "passive"))
      (node (ref "SLAVE-7") (pin "6") (pinfunction "6_6") (pintype "passive"))
      (node (ref "U$1") (pin "OUT+") (pinfunction "OUT+_OUT+") (pintype "bidirectional"))
      (node (ref "U$29") (pin "VIN") (pinfunction "VIN_VIN") (pintype "bidirectional"))
    )
    (net (code "140") (name "5V") (class "Default")
      (node (ref "IMU_BLOCK") (pin "4") (pinfunction "4_4") (pintype "bidirectional"))
      (node (ref "IMU_BLOCK-M") (pin "4") (pinfunction "4_4") (pintype "bidirectional"))
      (node (ref "JP1") (pin "3") (pinfunction "3_3") (pintype "passive"))
      (node (ref "M_ENC1") (pin "1") (pinfunction "1_1") (pintype "passive"))
      (node (ref "M_ENC1") (pin "5") (pinfunction "5_5") (pintype "passive"))
      (node (ref "PULL_RESISTOR-M") (pin "1") (pinfunction "1_1") (pintype "passive"))
      (node (ref "RN3") (pin "1") (pinfunction "1_1") (pintype "passive"))
      (node (ref "S-ENC") (pin "1") (pinfunction "1_1") (pintype "passive"))
      (node (ref "S1") (pin "3") (pinfunction "3_3") (pintype "passive"))
      (node (ref "S1") (pin "4") (pinfunction "4_4") (pintype "passive"))
      (node (ref "U$2") (pin "OUT+") (pinfunction "OUT+_OUT+") (pintype "bidirectional"))
      (node (ref "U$21") (pin "3") (pinfunction "3_3") (pintype "bidirectional"))
      (node (ref "U$22") (pin "3") (pinfunction "3_3") (pintype "bidirectional"))
      (node (ref "U$27") (pin "1") (pinfunction "1_1") (pintype "bidirectional"))
    )
    (net (code "141") (name "5VS") (class "Default")
      (node (ref "5V_GND") (pin "1") (pinfunction "1_1") (pintype "passive"))
      (node (ref "5V_GND") (pin "2") (pinfunction "2_2") (pintype "passive"))
      (node (ref "JP13") (pin "3") (pinfunction "3_3") (pintype "passive"))
      (node (ref "JP17") (pin "1") (pinfunction "1_1") (pintype "passive"))
      (node (ref "JP17") (pin "2") (pinfunction "2_2") (pintype "passive"))
      (node (ref "JP2") (pin "1") (pinfunction "1_1") (pintype "passive"))
      (node (ref "JP2") (pin "2") (pinfunction "2_2") (pintype "passive"))
      (node (ref "JP3") (pin "1") (pinfunction "1_1") (pintype "passive"))
      (node (ref "JP3") (pin "2") (pinfunction "2_2") (pintype "passive"))
      (node (ref "RST_VIN") (pin "4") (pinfunction "4_4") (pintype "passive"))
      (node (ref "S1") (pin "2") (pinfunction "2_2") (pintype "passive"))
      (node (ref "SV1") (pin "6") (pinfunction "6_6") (pintype "passive"))
      (node (ref "U$29") (pin "5V") (pinfunction "5V_5V") (pintype "bidirectional"))
      (node (ref "U$29") (pin "5V1") (pinfunction "5V1_5V1") (pintype "bidirectional"))
    )
    (net (code "142") (name "12V") (class "Default")
      (node (ref "MAIN_SUPPLY") (pin "3") (pinfunction "3_3") (pintype "bidirectional"))
      (node (ref "SABER_1") (pin "2") (pinfunction "2_2") (pintype "bidirectional"))
      (node (ref "SABER_2") (pin "2") (pinfunction "2_2") (pintype "bidirectional"))
      (node (ref "ULN") (pin "9") (pinfunction "9_9") (pintype "passive"))
    )
    (net (code "143") (name "12V_B") (class "Default")
      (node (ref "12V_B") (pin "2") (pinfunction "2_2") (pintype "bidirectional"))
      (node (ref "MAIN_SUPPLY") (pin "2") (pinfunction "2_2") (pintype "bidirectional"))
      (node (ref "MAIN_SUPPLY1") (pin "1") (pinfunction "1_1") (pintype "bidirectional"))
      (node (ref "MAIN_SUPPLY1") (pin "2") (pinfunction "2_2") (pintype "bidirectional"))
      (node (ref "U$1") (pin "IN+") (pinfunction "IN+_IN+") (pintype "bidirectional"))
      (node (ref "U$11") (pin "3") (pinfunction "3_3") (pintype "bidirectional"))
      (node (ref "U$16") (pin "3") (pinfunction "3_3") (pintype "bidirectional"))
      (node (ref "U$2") (pin "IN+") (pinfunction "IN+_IN+") (pintype "bidirectional"))
      (node (ref "U$4") (pin "3") (pinfunction "3_3") (pintype "bidirectional"))
      (node (ref "U$5") (pin "1") (pinfunction "1_1") (pintype "bidirectional"))
      (node (ref "U$5") (pin "2") (pinfunction "2_2") (pintype "bidirectional"))
      (node (ref "U$5") (pin "3") (pinfunction "3_3") (pintype "bidirectional"))
      (node (ref "U$6") (pin "3") (pinfunction "3_3") (pintype "bidirectional"))
    )
    (net (code "144") (name "D2") (class "Default")
      (node (ref "D7_RX0") (pin "6") (pinfunction "6_6") (pintype "passive"))
      (node (ref "JP6") (pin "3") (pinfunction "3_3") (pintype "passive"))
      (node (ref "M_ENC1") (pin "2") (pinfunction "2_2") (pintype "passive"))
      (node (ref "PULL_RESISTOR-M") (pin "2") (pinfunction "2_2") (pintype "passive"))
      (node (ref "U$29") (pin "D2") (pinfunction "D2_D2") (pintype "bidirectional"))
    )
    (net (code "145") (name "D3") (class "Default")
      (node (ref "D7_RX0") (pin "5") (pinfunction "5_5") (pintype "passive"))
      (node (ref "JP6") (pin "4") (pinfunction "4_4") (pintype "passive"))
      (node (ref "M_ENC1") (pin "6") (pinfunction "6_6") (pintype "passive"))
      (node (ref "PULL_RESISTOR-M") (pin "4") (pinfunction "4_4") (pintype "passive"))
      (node (ref "U$29") (pin "D3") (pinfunction "D3_D3") (pintype "bidirectional"))
    )
    (net (code "146") (name "D4") (class "Default")
      (node (ref "D7_RX0") (pin "4") (pinfunction "4_4") (pintype "passive"))
      (node (ref "JP6") (pin "5") (pinfunction "5_5") (pintype "passive"))
      (node (ref "M_ENC1") (pin "4") (pinfunction "4_4") (pintype "passive"))
      (node (ref "PULL_RESISTOR-M") (pin "3") (pinfunction "3_3") (pintype "passive"))
      (node (ref "U$29") (pin "D4") (pinfunction "D4_D4") (pintype "bidirectional"))
    )
    (net (code "147") (name "D6") (class "Default")
      (node (ref "D7_RX0") (pin "2") (pinfunction "2_2") (pintype "passive"))
      (node (ref "JP6") (pin "7") (pinfunction "7_7") (pintype "passive"))
      (node (ref "M_ENC1") (pin "8") (pinfunction "8_8") (pintype "passive"))
      (node (ref "PULL_RESISTOR-M") (pin "5") (pinfunction "5_5") (pintype "passive"))
      (node (ref "U$29") (pin "D6") (pinfunction "D6_D6") (pintype "bidirectional"))
    )
    (net (code "148") (name "GND") (class "Default")
      (node (ref "12V_B") (pin "1") (pinfunction "1_1") (pintype "bidirectional"))
      (node (ref "5V_GND") (pin "35") (pinfunction "35_35") (pintype "passive"))
      (node (ref "5V_GND") (pin "36") (pinfunction "36_36") (pintype "passive"))
      (node (ref "ESTOP") (pin "1") (pinfunction "1_1") (pintype "bidirectional"))
      (node (ref "IMU_BLOCK") (pin "3") (pinfunction "3_3") (pintype "bidirectional"))
      (node (ref "IMU_BLOCK-M") (pin "3") (pinfunction "3_3") (pintype "bidirectional"))
      (node (ref "JP1") (pin "1") (pinfunction "1_1") (pintype "passive"))
      (node (ref "JP13") (pin "4") (pinfunction "4_4") (pintype "passive"))
      (node (ref "JP13") (pin "5") (pinfunction "5_5") (pintype "passive"))
      (node (ref "JP17") (pin "35") (pinfunction "35_35") (pintype "passive"))
      (node (ref "JP17") (pin "36") (pinfunction "36_36") (pintype "passive"))
      (node (ref "JP5") (pin "1") (pinfunction "1_1") (pintype "passive"))
      (node (ref "JP5") (pin "2") (pinfunction "2_2") (pintype "passive"))
      (node (ref "JP7") (pin "1") (pinfunction "1_1") (pintype "passive"))
      (node (ref "JP7") (pin "2") (pinfunction "2_2") (pintype "passive"))
      (node (ref "LIMIT_SWITCH") (pin "3") (pinfunction "3_3") (pintype "bidirectional"))
      (node (ref "M_ENC1") (pin "3") (pinfunction "3_3") (pintype "passive"))
      (node (ref "M_ENC1") (pin "7") (pinfunction "7_7") (pintype "passive"))
      (node (ref "R2") (pin "1") (pinfunction "1_1") (pintype "passive"))
      (node (ref "R3") (pin "1") (pinfunction "1_1") (pintype "passive"))
      (node (ref "RESET") (pin "3") (pinfunction "2_3") (pintype "passive"))
      (node (ref "RN1") (pin "1") (pinfunction "1_1") (pintype "passive"))
      (node (ref "RST_VIN") (pin "2") (pinfunction "2_2") (pintype "passive"))
      (node (ref "RST_VIN") (pin "3") (pinfunction "3_3") (pintype "passive"))
      (node (ref "S-5V_GND1") (pin "35") (pinfunction "35_35") (pintype "passive"))
      (node (ref "S-5V_GND1") (pin "36") (pinfunction "36_36") (pintype "passive"))
      (node (ref "S-D8_D13") (pin "4") (pinfunction "4_4") (pintype "passive"))
      (node (ref "S-RST_VIN1") (pin "2") (pinfunction "2_2") (pintype "passive"))
      (node (ref "S-RST_VIN1") (pin "3") (pinfunction "3_3") (pintype "passive"))
      (node (ref "SABER1") (pin "2") (pinfunction "2_2") (pintype "passive"))
      (node (ref "SABER2") (pin "2") (pinfunction "2_2") (pintype "passive"))
      (node (ref "SABER_1") (pin "1") (pinfunction "1_1") (pintype "bidirectional"))
      (node (ref "SABER_2") (pin "1") (pinfunction "1_1") (pintype "bidirectional"))
      (node (ref "SG1") (pin "-") (pinfunction "2_-") (pintype "passive"))
      (node (ref "SLAVE-4") (pin "35") (pinfunction "35_35") (pintype "passive"))
      (node (ref "SLAVE-4") (pin "36") (pinfunction "36_36") (pintype "passive"))
      (node (ref "SLAVE-7") (pin "4") (pinfunction "4_4") (pintype "passive"))
      (node (ref "SLAVE-7") (pin "5") (pinfunction "5_5") (pintype "passive"))
      (node (ref "SV1") (pin "2") (pinfunction "2_2") (pintype "passive"))
      (node (ref "SV2") (pin "2") (pinfunction "2_2") (pintype "passive"))
      (node (ref "SV3") (pin "2") (pinfunction "2_2") (pintype "passive"))
      (node (ref "U$1") (pin "IN-") (pinfunction "IN-_IN-") (pintype "bidirectional"))
      (node (ref "U$1") (pin "OUT-") (pinfunction "OUT-_OUT-") (pintype "bidirectional"))
      (node (ref "U$10") (pin "1") (pinfunction "1_1") (pintype "bidirectional"))
      (node (ref "U$10") (pin "2") (pinfunction "2_2") (pintype "bidirectional"))
      (node (ref "U$10") (pin "3") (pinfunction "3_3") (pintype "bidirectional"))
      (node (ref "U$11") (pin "1") (pinfunction "1_1") (pintype "bidirectional"))
      (node (ref "U$16") (pin "1") (pinfunction "1_1") (pintype "bidirectional"))
      (node (ref "U$17") (pin "2") (pinfunction "GND_2") (pintype "bidirectional"))
      (node (ref "U$18") (pin "2") (pinfunction "GND_2") (pintype "bidirectional"))
      (node (ref "U$19") (pin "2") (pinfunction "GND_2") (pintype "bidirectional"))
      (node (ref "U$2") (pin "IN-") (pinfunction "IN-_IN-") (pintype "bidirectional"))
      (node (ref "U$2") (pin "OUT-") (pinfunction "OUT-_OUT-") (pintype "bidirectional"))
      (node (ref "U$20") (pin "2") (pinfunction "GND_2") (pintype "bidirectional"))
      (node (ref "U$21") (pin "4") (pinfunction "4_4") (pintype "bidirectional"))
      (node (ref "U$22") (pin "4") (pinfunction "4_4") (pintype "bidirectional"))
      (node (ref "U$27") (pin "2") (pinfunction "2_2") (pintype "bidirectional"))
      (node (ref "U$28") (pin "1") (pinfunction "1_1") (pintype "bidirectional"))
      (node (ref "U$29") (pin "GND") (pinfunction "GND_GND") (pintype "bidirectional"))
      (node (ref "U$29") (pin "GND1") (pinfunction "GD_GND1") (pintype "bidirectional"))
      (node (ref "U$29") (pin "GND2") (pinfunction "GND2_GND2") (pintype "bidirectional"))
      (node (ref "U$29") (pin "GND3") (pinfunction "GND3_GND3") (pintype "bidirectional"))
      (node (ref "U$4") (pin "1") (pinfunction "1_1") (pintype "bidirectional"))
      (node (ref "U$6") (pin "1") (pinfunction "1_1") (pintype "bidirectional"))
      (node (ref "U$8") (pin "2") (pinfunction "2_2") (pintype "bidirectional"))
      (node (ref "ULN") (pin "8") (pinfunction "8_8") (pintype "passive"))
    )
    (net (code "149") (name "MISO") (class "Default")
      (node (ref "SV1") (pin "5") (pinfunction "5_5") (pintype "passive"))
      (node (ref "U$29") (pin "MISO") (pinfunction "MI_MISO") (pintype "bidirectional"))
    )
    (net (code "150") (name "MOSI") (class "Default")
      (node (ref "SV1") (pin "4") (pinfunction "4_4") (pintype "passive"))
      (node (ref "U$29") (pin "MOSI") (pinfunction "MO_MOSI") (pintype "bidirectional"))
    )
    (net (code "151") (name "NC") (class "Default")
      (node (ref "JP1") (pin "2") (pinfunction "2_2") (pintype "passive"))
    )
    (net (code "152") (name "Net-(D1-C)") (class "Default")
      (node (ref "D1") (pin "K") (pinfunction "C_K") (pintype "passive"))
      (node (ref "RN1") (pin "2") (pinfunction "2_2") (pintype "passive"))
    )
    (net (code "153") (name "Net-(D2-C)") (class "Default")
      (node (ref "D2") (pin "K") (pinfunction "C_K") (pintype "passive"))
      (node (ref "RN1") (pin "3") (pinfunction "3_3") (pintype "passive"))
    )
    (net (code "154") (name "Net-(D3-C)") (class "Default")
      (node (ref "D3") (pin "K") (pinfunction "C_K") (pintype "passive"))
      (node (ref "RN1") (pin "4") (pinfunction "4_4") (pintype "passive"))
    )
    (net (code "155") (name "Net-(D4-C)") (class "Default")
      (node (ref "D4") (pin "K") (pinfunction "C_K") (pintype "passive"))
      (node (ref "RN1") (pin "5") (pinfunction "5_5") (pintype "passive"))
    )
    (net (code "156") (name "Net-(D5-C)") (class "Default")
      (node (ref "D5") (pin "K") (pinfunction "C_K") (pintype "passive"))
      (node (ref "R3") (pin "2") (pinfunction "2_2") (pintype "passive"))
    )
    (net (code "157") (name "Net-(D6-C)") (class "Default")
      (node (ref "D6") (pin "K") (pinfunction "C_K") (pintype "passive"))
      (node (ref "U$7") (pin "3") (pinfunction "3_3") (pintype "bidirectional"))
      (node (ref "ULN") (pin "16") (pinfunction "16_16") (pintype "passive"))
    )
    (net (code "158") (name "Net-(D6-PadA)") (class "Default")
      (node (ref "D6") (pin "A") (pinfunction "A_A") (pintype "passive"))
      (node (ref "RN3") (pin "2") (pinfunction "2_2") (pintype "passive"))
    )
    (net (code "159") (name "Net-(D7-C)") (class "Default")
      (node (ref "D7") (pin "K") (pinfunction "C_K") (pintype "passive"))
      (node (ref "U$7") (pin "2") (pinfunction "2_2") (pintype "bidirectional"))
      (node (ref "ULN") (pin "15") (pinfunction "15_15") (pintype "passive"))
    )
    (net (code "160") (name "Net-(D7-PadA)") (class "Default")
      (node (ref "D7") (pin "A") (pinfunction "A_A") (pintype "passive"))
      (node (ref "RN3") (pin "3") (pinfunction "3_3") (pintype "passive"))
    )
    (net (code "161") (name "Net-(D8-C)") (class "Default")
      (node (ref "D8") (pin "K") (pinfunction "C_K") (pintype "passive"))
      (node (ref "U$7") (pin "1") (pinfunction "1_1") (pintype "bidirectional"))
      (node (ref "ULN") (pin "14") (pinfunction "14_14") (pintype "passive"))
    )
    (net (code "162") (name "Net-(D8-PadA)") (class "Default")
      (node (ref "D8") (pin "A") (pinfunction "A_A") (pintype "passive"))
      (node (ref "RN3") (pin "4") (pinfunction "4_4") (pintype "passive"))
    )
    (net (code "163") (name "Net-(D9-C)") (class "Default")
      (node (ref "D9") (pin "K") (pinfunction "C_K") (pintype "passive"))
      (node (ref "MAIN_SUPPLY1") (pin "3") (pinfunction "3_3") (pintype "bidirectional"))
      (node (ref "ULN") (pin "13") (pinfunction "13_13") (pintype "passive"))
    )
    (net (code "164") (name "Net-(D9-PadA)") (class "Default")
      (node (ref "D9") (pin "A") (pinfunction "A_A") (pintype "passive"))
      (node (ref "RN3") (pin "5") (pinfunction "5_5") (pintype "passive"))
    )
    (net (code "165") (name "Net-(D13-C)") (class "Default")
      (node (ref "D13") (pin "K") (pinfunction "C_K") (pintype "passive"))
      (node (ref "R2") (pin "2") (pinfunction "2_2") (pintype "passive"))
    )
    (net (code "166") (name "Net-(RESET-Pad1)") (class "Default")
      (node (ref "RESET") (pin "1") (pinfunction "1_1") (pintype "passive"))
      (node (ref "S4") (pin "3") (pinfunction "3_3") (pintype "passive"))
      (node (ref "S4") (pin "4") (pinfunction "4_4") (pintype "passive"))
    )
    (net (code "167") (name "Net-(SG1-1)") (class "Default")
      (node (ref "BUZZ-S") (pin "1") (pinfunction "1_1") (pintype "passive"))
      (node (ref "BUZZ_M") (pin "1") (pinfunction "1_1") (pintype "passive"))
      (node (ref "SG1") (pin "+") (pinfunction "1_+") (pintype "passive"))
    )
    (net (code "168") (name "RST") (class "Default")
      (node (ref "JP13") (pin "1") (pinfunction "1_1") (pintype "passive"))
      (node (ref "RST_VIN") (pin "6") (pinfunction "6_6") (pintype "passive"))
      (node (ref "S4") (pin "1") (pinfunction "1_1") (pintype "passive"))
      (node (ref "SV1") (pin "1") (pinfunction "1_1") (pintype "passive"))
      (node (ref "U$29") (pin "RST") (pinfunction "RST_RST") (pintype "bidirectional"))
      (node (ref "U$29") (pin "RST1") (pinfunction "RST1_RST1") (pintype "bidirectional"))
    )
    (net (code "169") (name "S-5VS") (class "Default")
      (node (ref "S-5V_GND1") (pin "1") (pinfunction "1_1") (pintype "passive"))
      (node (ref "S-5V_GND1") (pin "2") (pinfunction "2_2") (pintype "passive"))
      (node (ref "S-RST_VIN1") (pin "4") (pinfunction "4_4") (pintype "passive"))
      (node (ref "S1") (pin "1") (pinfunction "1_1") (pintype "passive"))
      (node (ref "SLAVE-4") (pin "1") (pinfunction "1_1") (pintype "passive"))
      (node (ref "SLAVE-4") (pin "2") (pinfunction "2_2") (pintype "passive"))
      (node (ref "SLAVE-7") (pin "3") (pinfunction "3_3") (pintype "passive"))
      (node (ref "SV2") (pin "6") (pinfunction "6_6") (pintype "passive"))
      (node (ref "SV3") (pin "6") (pinfunction "6_6") (pintype "passive"))
    )
    (net (code "170") (name "S-D2") (class "Default")
      (node (ref "S-D7_RX0") (pin "6") (pinfunction "6_6") (pintype "passive"))
      (node (ref "S-ENC") (pin "4") (pinfunction "4_4") (pintype "passive"))
      (node (ref "SLAVE-2") (pin "3") (pinfunction "3_3") (pintype "passive"))
      (node (ref "U$21") (pin "2") (pinfunction "2_2") (pintype "bidirectional"))
    )
    (net (code "171") (name "S-D3") (class "Default")
      (node (ref "S-D7_RX0") (pin "5") (pinfunction "5_5") (pintype "passive"))
      (node (ref "S-ENC") (pin "2") (pinfunction "2_2") (pintype "passive"))
      (node (ref "SLAVE-2") (pin "4") (pinfunction "4_4") (pintype "passive"))
      (node (ref "U$22") (pin "2") (pinfunction "2_2") (pintype "bidirectional"))
    )
    (net (code "172") (name "S-D4") (class "Default")
      (node (ref "S-D7_RX0") (pin "4") (pinfunction "4_4") (pintype "passive"))
      (node (ref "S-ENC") (pin "5") (pinfunction "5_5") (pintype "passive"))
      (node (ref "SLAVE-2") (pin "5") (pinfunction "5_5") (pintype "passive"))
      (node (ref "U$21") (pin "1") (pinfunction "1_1") (pintype "bidirectional"))
    )
    (net (code "173") (name "S-D5") (class "Default")
      (node (ref "JP1") (pin "6") (pinfunction "6_6") (pintype "passive"))
      (node (ref "S-D7_RX0") (pin "3") (pinfunction "3_3") (pintype "passive"))
      (node (ref "SLAVE-2") (pin "6") (pinfunction "6_6") (pintype "passive"))
    )
    (net (code "174") (name "S-D6") (class "Default")
      (node (ref "S-D7_RX0") (pin "2") (pinfunction "2_2") (pintype "passive"))
      (node (ref "S-ENC") (pin "3") (pinfunction "3_3") (pintype "passive"))
      (node (ref "SLAVE-2") (pin "7") (pinfunction "7_7") (pintype "passive"))
      (node (ref "U$22") (pin "1") (pinfunction "1_1") (pintype "bidirectional"))
    )
    (net (code "175") (name "S-MISO") (class "Default")
      (node (ref "SV2") (pin "5") (pinfunction "5_5") (pintype "passive"))
      (node (ref "SV3") (pin "5") (pinfunction "5_5") (pintype "passive"))
    )
    (net (code "176") (name "S-MOSI") (class "Default")
      (node (ref "SV2") (pin "4") (pinfunction "4_4") (pintype "passive"))
      (node (ref "SV3") (pin "4") (pinfunction "4_4") (pintype "passive"))
    )
    (net (code "177") (name "S-RST") (class "Default")
      (node (ref "S-RST_VIN1") (pin "6") (pinfunction "6_6") (pintype "passive"))
      (node (ref "S4") (pin "2") (pinfunction "2_2") (pintype "passive"))
      (node (ref "SLAVE-7") (pin "1") (pinfunction "1_1") (pintype "passive"))
      (node (ref "SV2") (pin "1") (pinfunction "1_1") (pintype "passive"))
      (node (ref "SV3") (pin "1") (pinfunction "1_1") (pintype "passive"))
    )
    (net (code "178") (name "S-RX3") (class "Default")
      (node (ref "JP1") (pin "4") (pinfunction "4_4") (pintype "passive"))
      (node (ref "S-TX3_SCL1") (pin "2") (pinfunction "2_2") (pintype "passive"))
      (node (ref "SLAVE-3") (pin "7") (pinfunction "7_7") (pintype "passive"))
    )
    (net (code "179") (name "S-SCK") (class "Default")
      (node (ref "SV2") (pin "3") (pinfunction "3_3") (pintype "passive"))
      (node (ref "SV3") (pin "3") (pinfunction "3_3") (pintype "passive"))
    )
    (net (code "180") (name "S-SCL") (class "Default")
      (node (ref "IMU_BLOCK") (pin "1") (pinfunction "1_1") (pintype "bidirectional"))
      (node (ref "S-TX3_SCL1") (pin "8") (pinfunction "8_8") (pintype "passive"))
      (node (ref "SLAVE-3") (pin "1") (pinfunction "1_1") (pintype "passive"))
    )
    (net (code "181") (name "S-SDA") (class "Default")
      (node (ref "IMU_BLOCK") (pin "2") (pinfunction "2_2") (pintype "bidirectional"))
      (node (ref "S-TX3_SCL1") (pin "7") (pinfunction "7_7") (pintype "passive"))
      (node (ref "SLAVE-3") (pin "2") (pinfunction "2_2") (pintype "passive"))
    )
    (net (code "182") (name "S-TX3") (class "Default")
      (node (ref "JP1") (pin "5") (pinfunction "5_5") (pintype "passive"))
      (node (ref "S-TX3_SCL1") (pin "1") (pinfunction "1_1") (pintype "passive"))
      (node (ref "SLAVE-3") (pin "8") (pinfunction "8_8") (pintype "passive"))
    )
    (net (code "183") (name "SCK") (class "Default")
      (node (ref "SV1") (pin "3") (pinfunction "3_3") (pintype "passive"))
      (node (ref "U$29") (pin "SCK") (pinfunction "SC_SCK") (pintype "bidirectional"))
    )
    (net (code "184") (name "SCL") (class "Default")
      (node (ref "IMU_BLOCK-M") (pin "2") (pinfunction "2_2") (pintype "bidirectional"))
      (node (ref "JP8") (pin "1") (pinfunction "1_1") (pintype "passive"))
      (node (ref "TX3_SCL") (pin "8") (pinfunction "8_8") (pintype "passive"))
      (node (ref "U$29") (pin "SCL") (pinfunction "SCL_SCL") (pintype "bidirectional"))
    )
    (net (code "185") (name "SDA") (class "Default")
      (node (ref "IMU_BLOCK-M") (pin "1") (pinfunction "1_1") (pintype "bidirectional"))
      (node (ref "JP8") (pin "2") (pinfunction "2_2") (pintype "passive"))
      (node (ref "TX3_SCL") (pin "7") (pinfunction "7_7") (pintype "passive"))
      (node (ref "U$29") (pin "SDA") (pinfunction "SDA_SDA") (pintype "bidirectional"))
    )
    (net (code "186") (name "unconnected-(RST_VIN-Pad7)") (class "Default")
      (node (ref "RST_VIN") (pin "7") (pinfunction "7_7") (pintype "passive"))
    )
    (net (code "187") (name "unconnected-(RST_VIN-Pad8)") (class "Default")
      (node (ref "RST_VIN") (pin "8") (pinfunction "8_8") (pintype "passive"))
    )
    (net (code "188") (name "unconnected-(S-RST_VIN1-Pad7)") (class "Default")
      (node (ref "S-RST_VIN1") (pin "7") (pinfunction "7_7") (pintype "passive"))
    )
    (net (code "189") (name "unconnected-(S-RST_VIN1-Pad8)") (class "Default")
      (node (ref "S-RST_VIN1") (pin "8") (pinfunction "8_8") (pintype "passive"))
    )
    (net (code "190") (name "unconnected-(U$9-Pad1)") (class "Default")
      (node (ref "U$9") (pin "1") (pinfunction "1_1") (pintype "bidirectional"))
    )
    (net (code "191") (name "unconnected-(U$15-Pad1)") (class "Default")
      (node (ref "U$15") (pin "1") (pinfunction "1_1") (pintype "bidirectional"))
    )
    (net (code "192") (name "unconnected-(U$23-Pad1)") (class "Default")
      (node (ref "U$23") (pin "1") (pinfunction "1_1") (pintype "bidirectional"))
    )
    (net (code "193") (name "unconnected-(U$24-Pad1)") (class "Default")
      (node (ref "U$24") (pin "1") (pinfunction "1_1") (pintype "bidirectional"))
    )
    (net (code "194") (name "unconnected-(U$25-Pad1)") (class "Default")
      (node (ref "U$25") (pin "1") (pinfunction "1_1") (pintype "bidirectional"))
    )
    (net (code "195") (name "unconnected-(U$26-Pad1)") (class "Default")
      (node (ref "U$26") (pin "1") (pinfunction "1_1") (pintype "bidirectional"))
    )
    (net (code "196") (name "unconnected-(U$29-Pad-)") (class "Default")
      (node (ref "U$29") (pin "-") (pinfunction "-_-") (pintype "bidirectional"))
    )
    (net (code "197") (name "unconnected-(U$29-PadAREF)") (class "Default")
      (node (ref "U$29") (pin "AREF") (pinfunction "AREF_AREF") (pintype "bidirectional"))
    )
    (net (code "198") (name "unconnected-(U$29-PadVREF)") (class "Default")
      (node (ref "U$29") (pin "VREF") (pinfunction "VREF_VREF") (pintype "bidirectional"))
    )
    (net (code "199") (name "unconnected-(ULN-Pad5)") (class "Default")
      (node (ref "ULN") (pin "5") (pinfunction "5_5") (pintype "passive"))
    )
    (net (code "200") (name "unconnected-(ULN-Pad6)") (class "Default")
      (node (ref "ULN") (pin "6") (pinfunction "6_6") (pintype "passive"))
    )
    (net (code "201") (name "unconnected-(ULN-Pad7)") (class "Default")
      (node (ref "ULN") (pin "7") (pinfunction "7_7") (pintype "passive"))
    )
    (net (code "202") (name "unconnected-(ULN-Pad10)") (class "Default")
      (node (ref "ULN") (pin "10") (pinfunction "10_10") (pintype "passive"))
    )
    (net (code "203") (name "unconnected-(ULN-Pad11)") (class "Default")
      (node (ref "ULN") (pin "11") (pinfunction "11_11") (pintype "passive"))
    )
    (net (code "204") (name "unconnected-(ULN-Pad12)") (class "Default")
      (node (ref "ULN") (pin "12") (pinfunction "12_12") (pintype "passive"))
    )
  )
)
